# uSlices_v3.net
KiCad netlist of a schematic drawn in EAGLE
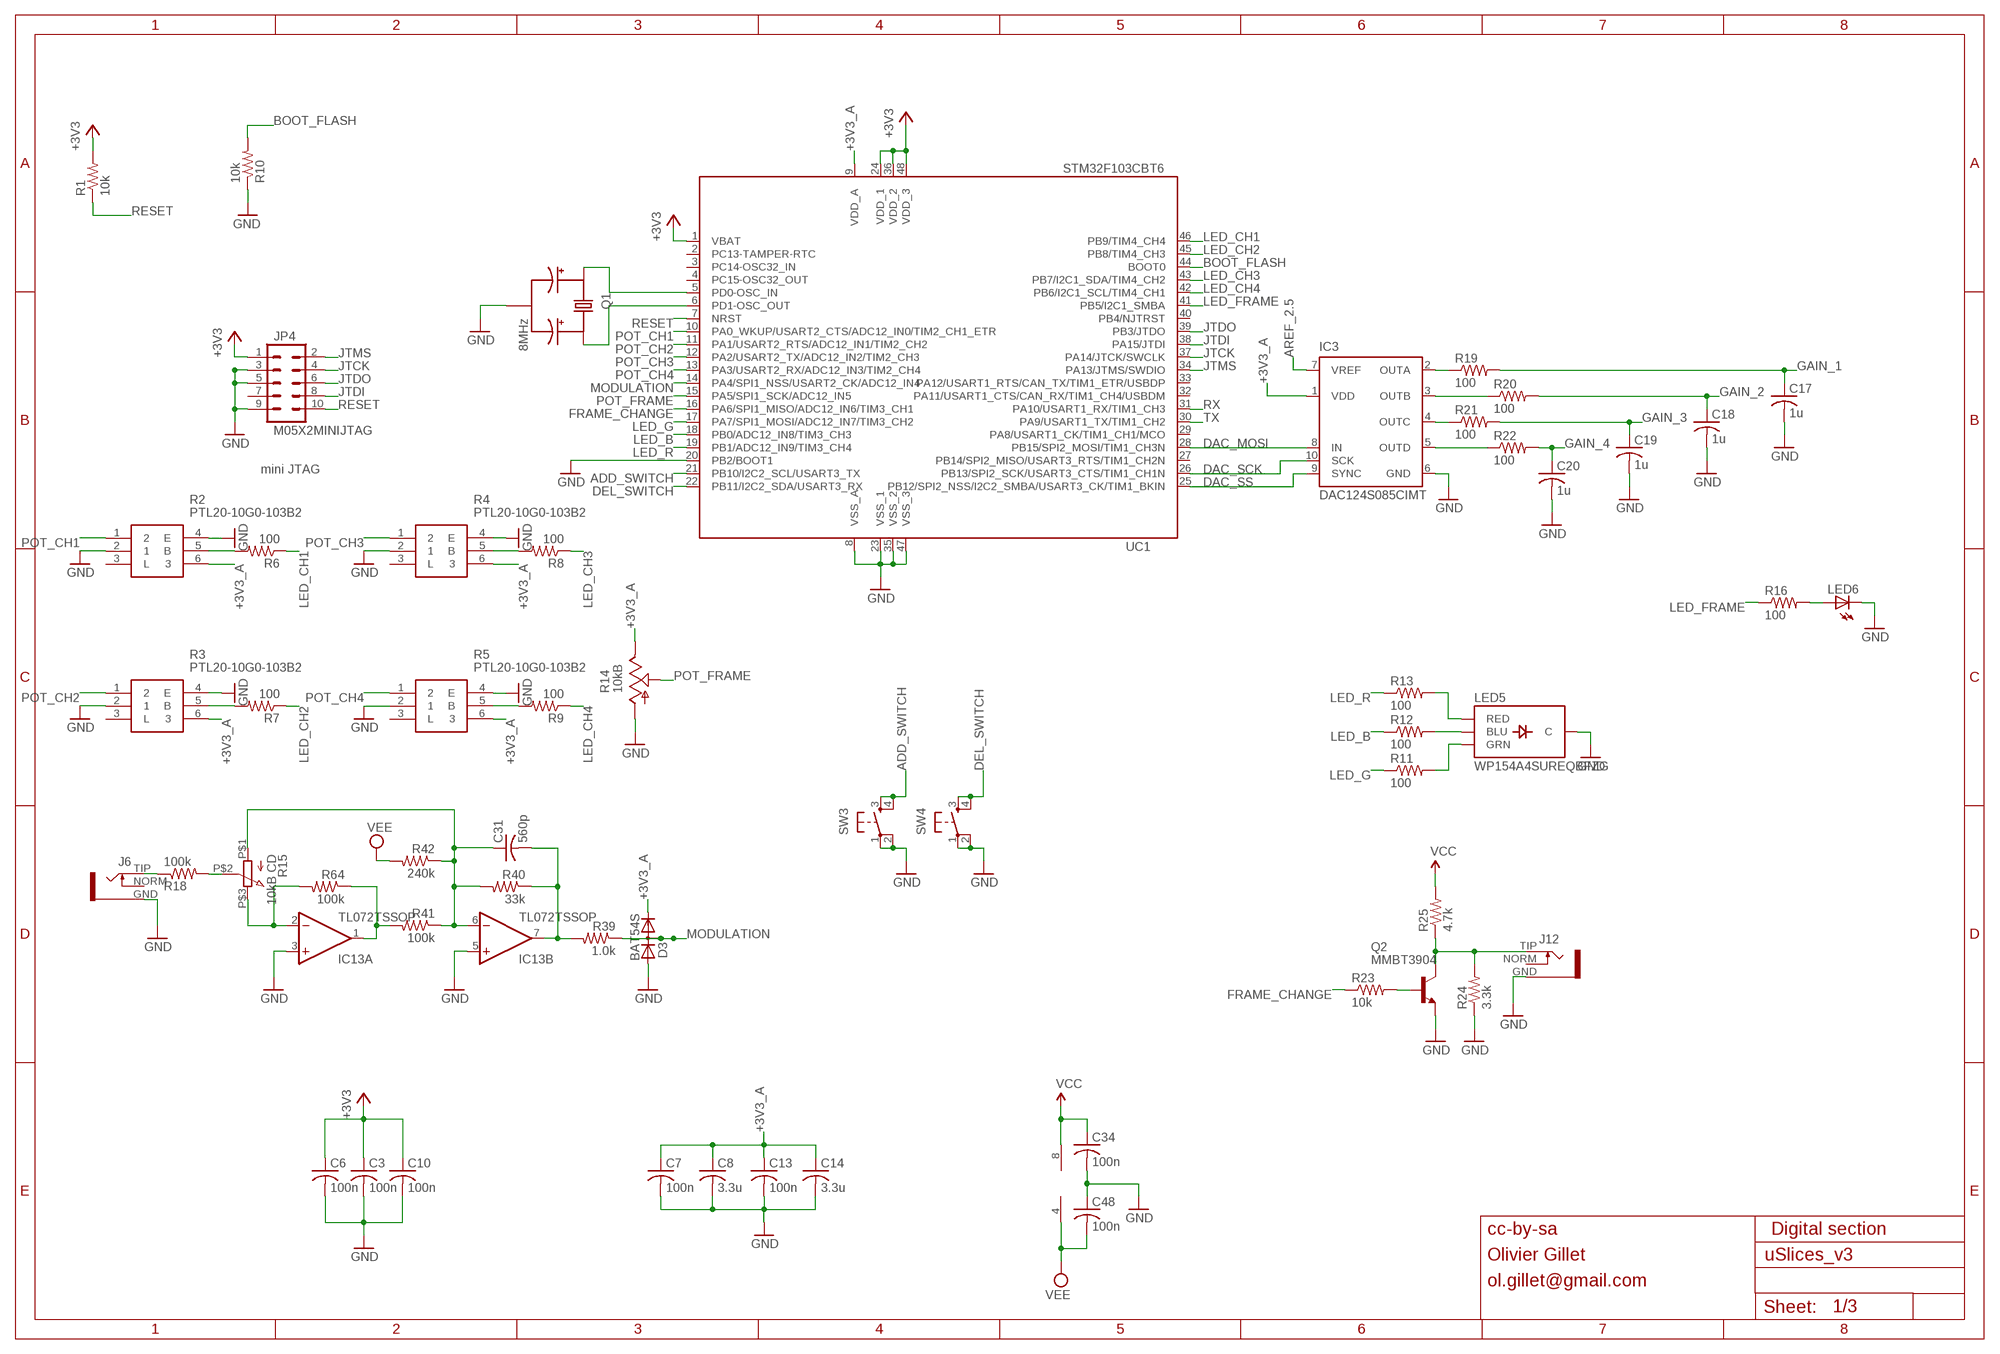
[diagram p0: schematic, sheet 1]
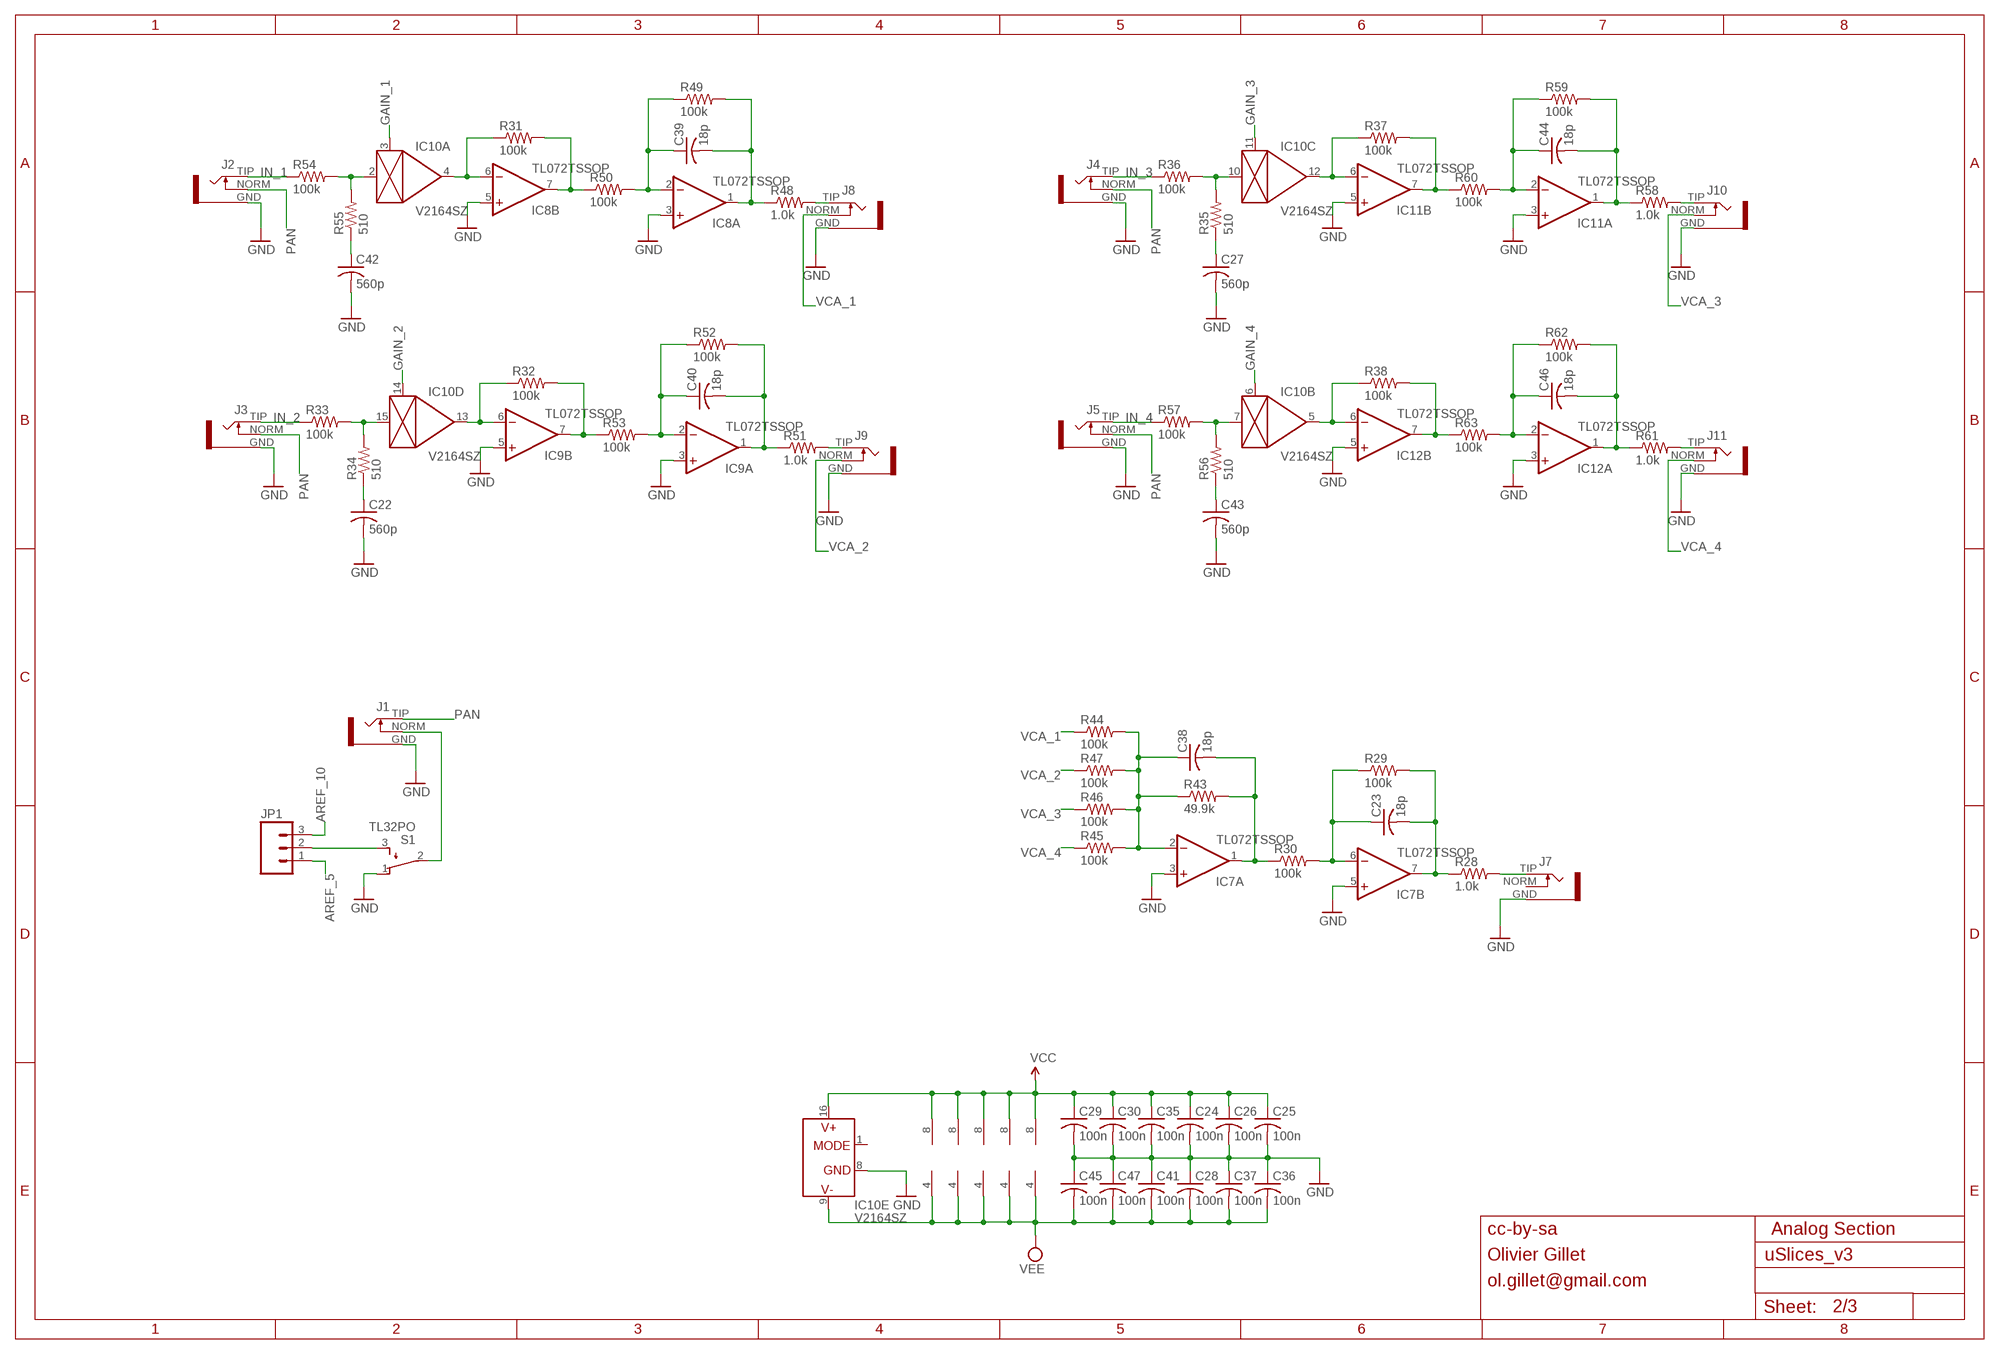
[diagram p1: schematic, sheet 2]
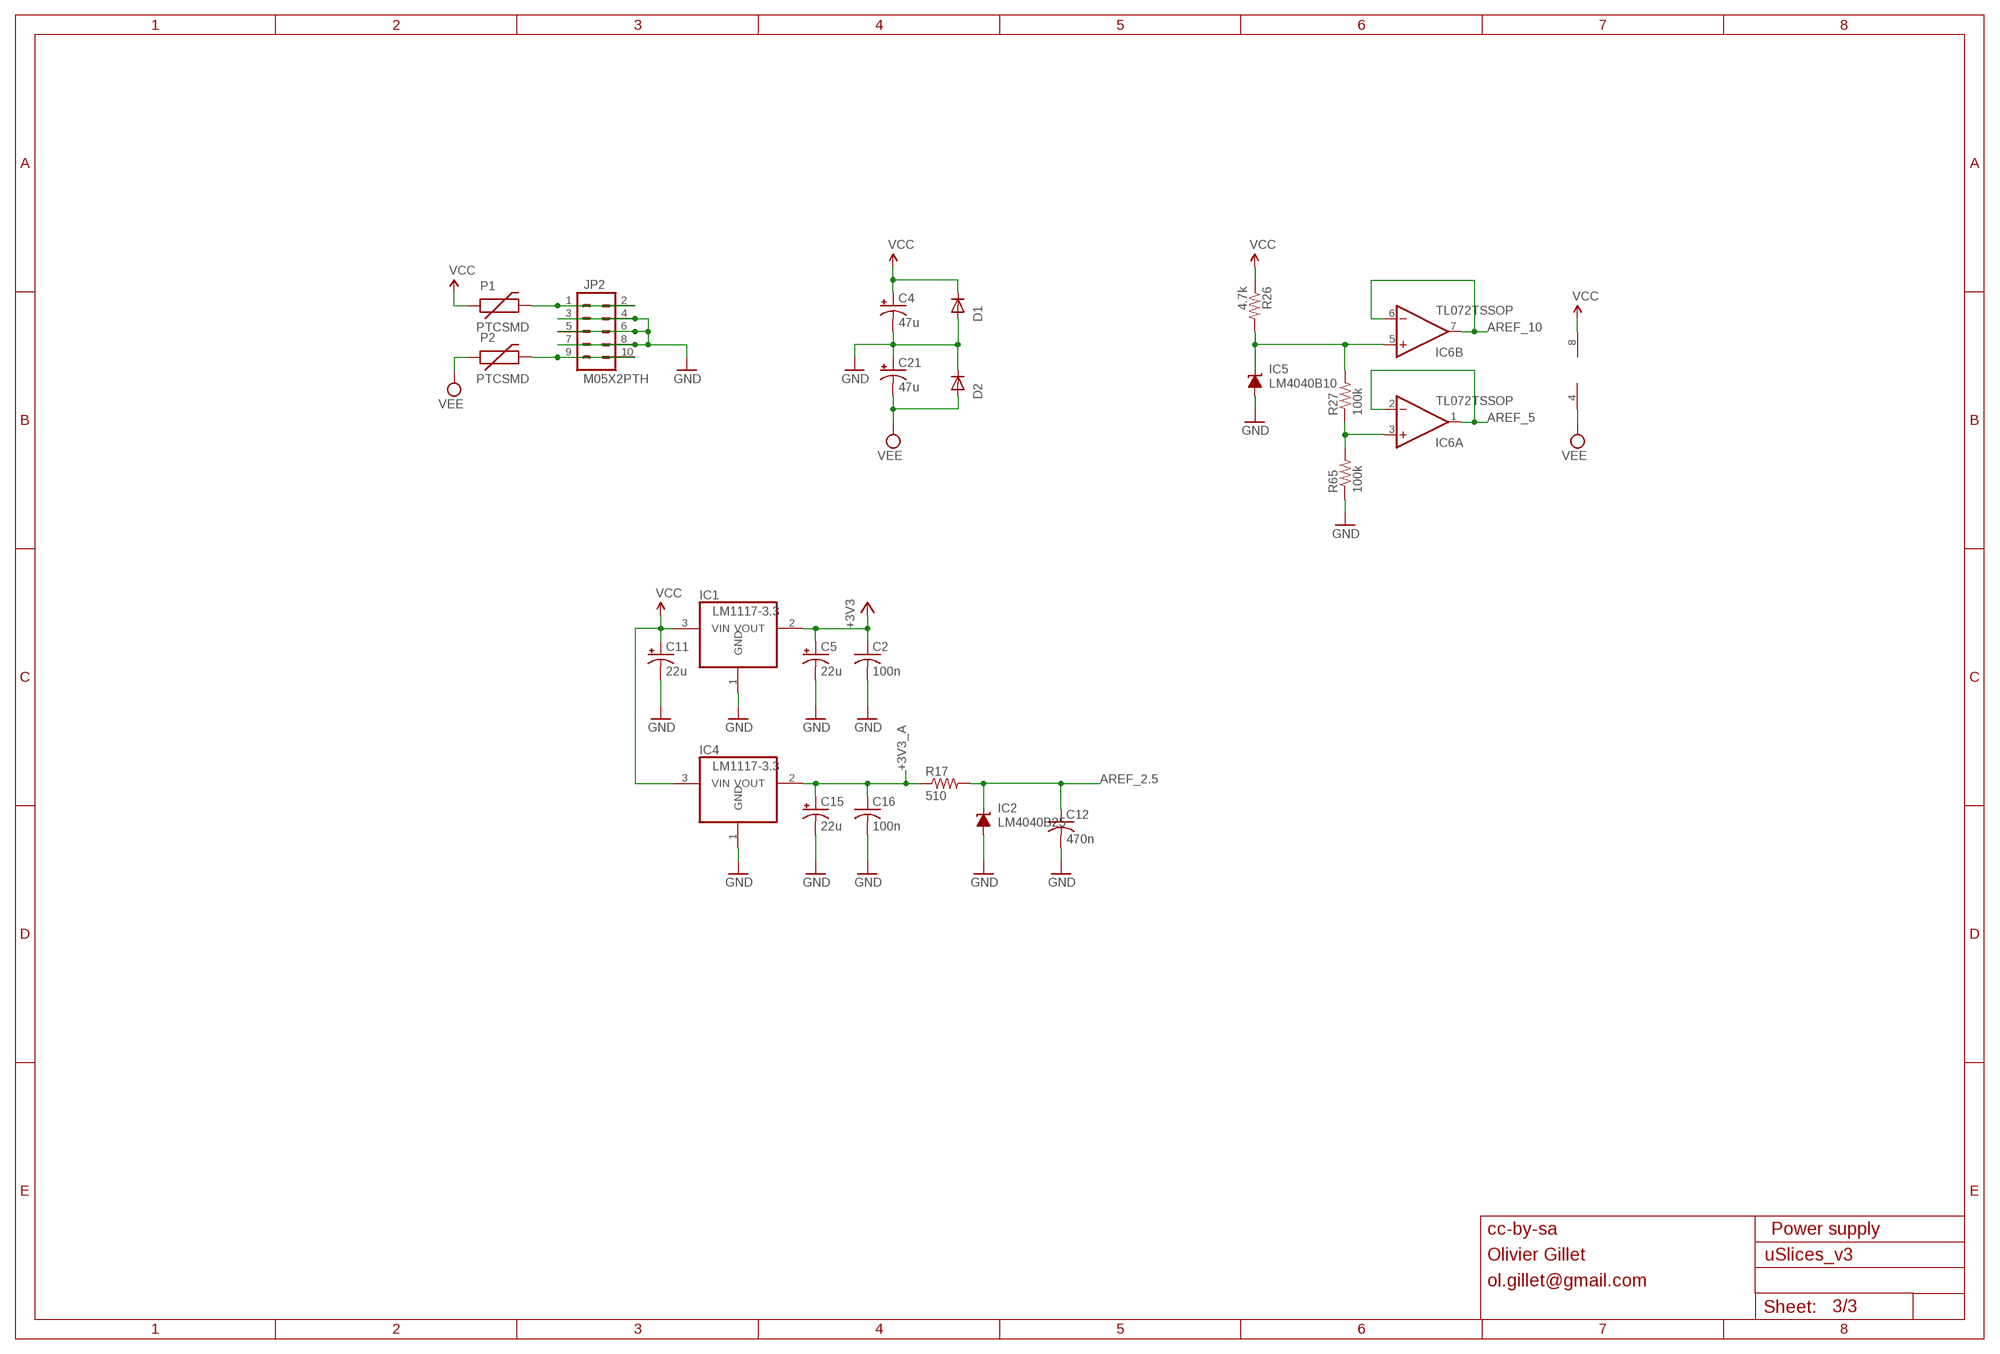
[diagram p2: schematic, sheet 3]

(export (version "E")
  (design (tool "Eeschema 10.0.6"))
  (components
    (comp (ref "C3")
      (value "100n")
      (footprint "eagle-import:C0603")
      (libsource (lib "eagle-import") (part "C-USC0603"))
    )
    (comp (ref "C6")
      (value "100n")
      (footprint "eagle-import:C0603")
      (libsource (lib "eagle-import") (part "C-USC0603"))
    )
    (comp (ref "C7")
      (value "100n")
      (footprint "eagle-import:C0603")
      (libsource (lib "eagle-import") (part "C-USC0603"))
    )
    (comp (ref "C8")
      (value "3.3u")
      (footprint "eagle-import:C0603")
      (libsource (lib "eagle-import") (part "C-USC0603"))
    )
    (comp (ref "C10")
      (value "100n")
      (footprint "eagle-import:C0603")
      (libsource (lib "eagle-import") (part "C-USC0603"))
    )
    (comp (ref "C13")
      (value "100n")
      (footprint "eagle-import:C0603")
      (libsource (lib "eagle-import") (part "C-USC0603"))
    )
    (comp (ref "C14")
      (value "3.3u")
      (footprint "eagle-import:C0603")
      (libsource (lib "eagle-import") (part "C-USC0603"))
    )
    (comp (ref "C17")
      (value "1u")
      (footprint "eagle-import:C0603")
      (libsource (lib "eagle-import") (part "C-USC0603"))
    )
    (comp (ref "C18")
      (value "1u")
      (footprint "eagle-import:C0603")
      (libsource (lib "eagle-import") (part "C-USC0603"))
    )
    (comp (ref "C19")
      (value "1u")
      (footprint "eagle-import:C0603")
      (libsource (lib "eagle-import") (part "C-USC0603"))
    )
    (comp (ref "C20")
      (value "1u")
      (footprint "eagle-import:C0603")
      (libsource (lib "eagle-import") (part "C-USC0603"))
    )
    (comp (ref "C31")
      (value "560p")
      (footprint "eagle-import:C0603")
      (libsource (lib "eagle-import") (part "C-USC0603"))
    )
    (comp (ref "C34")
      (value "100n")
      (footprint "eagle-import:C0603")
      (libsource (lib "eagle-import") (part "C-USC0603"))
    )
    (comp (ref "C48")
      (value "100n")
      (footprint "eagle-import:C0603")
      (libsource (lib "eagle-import") (part "C-USC0603"))
    )
    (comp (ref "D3")
      (value "BAT54S")
      (footprint "eagle-import:SOT23")
      (libsource (lib "eagle-import") (part "DIODE_2CACA-SOT23"))
    )
    (comp (ref "IC3")
      (value "DAC124S085CIMT")
      (footprint "eagle-import:MSOP10")
      (libsource (lib "eagle-import") (part "DAC124S085CIMT"))
    )
    (comp (ref "IC13")
      (value "TL072TSSOP")
      (footprint "eagle-import:TSSOP-8")
      (libsource (lib "eagle-import") (part "TL072TSSOP"))
    )
    (comp (ref "J6")
      (value "INSTRUO_S_JACK_S2_INV")
      (footprint "eagle-import:INSTRUO_S_JACK_S2_INV")
      (libsource (lib "eagle-import") (part "INSTRUO_S_JACK_S2_INV"))
    )
    (comp (ref "J12")
      (value "INSTRUO_S_JACK_S2_INV")
      (footprint "eagle-import:INSTRUO_S_JACK_S2_INV")
      (libsource (lib "eagle-import") (part "INSTRUO_S_JACK_S2_INV"))
    )
    (comp (ref "JP4")
      (value "M05X2MINIJTAG")
      (footprint "eagle-import:2X5-1.27")
      (libsource (lib "eagle-import") (part "M05X2MINIJTAG"))
    )
    (comp (ref "LED5")
      (value "WP154A4SUREQBFZG")
      (footprint "eagle-import:LED-TRICOLOR-THROUGHHOLE")
      (libsource (lib "eagle-import") (part "LED-TRICOLOR-THROUGHHOLE"))
    )
    (comp (ref "LED6")
      (value "LED3MM")
      (footprint "eagle-import:LED3MM")
      (libsource (lib "eagle-import") (part "LED3MM"))
    )
    (comp (ref "Q1")
      (value "8MHz")
      (footprint "eagle-import:INSTRUO_CRYSTAL_SMALLER")
      (libsource (lib "eagle-import") (part "INSTRUO_CRYSTAL_SMALLER"))
    )
    (comp (ref "Q2")
      (value "MMBT3904")
      (footprint "eagle-import:SOT23-BEC")
      (libsource (lib "eagle-import") (part "-NPN-SOT23-BECMMBT3904LT1"))
    )
    (comp (ref "R1")
      (value "10k")
      (footprint "eagle-import:R0603")
      (libsource (lib "eagle-import") (part "R-US_R0603"))
    )
    (comp (ref "R2")
      (value "PTL20-10G0-103B2")
      (footprint "eagle-import:PTL2010G0103B2")
      (fields (field (name "ARROW_PART_NUMBER") "PTL30-10O1-103B2"))
      (libsource (lib "eagle-import") (part "PTL20-10G0-103B2"))
    )
    (comp (ref "R3")
      (value "PTL20-10G0-103B2")
      (footprint "eagle-import:PTL2010G0103B2")
      (fields (field (name "ARROW_PART_NUMBER") "PTL30-10O1-103B2"))
      (libsource (lib "eagle-import") (part "PTL20-10G0-103B2"))
    )
    (comp (ref "R4")
      (value "PTL20-10G0-103B2")
      (footprint "eagle-import:PTL2010G0103B2")
      (fields (field (name "ARROW_PART_NUMBER") "PTL30-10O1-103B2"))
      (libsource (lib "eagle-import") (part "PTL20-10G0-103B2"))
    )
    (comp (ref "R5")
      (value "PTL20-10G0-103B2")
      (footprint "eagle-import:PTL2010G0103B2")
      (fields (field (name "ARROW_PART_NUMBER") "PTL30-10O1-103B2"))
      (libsource (lib "eagle-import") (part "PTL20-10G0-103B2"))
    )
    (comp (ref "R6")
      (value "100")
      (footprint "eagle-import:R0603")
      (libsource (lib "eagle-import") (part "R-US_R0603"))
    )
    (comp (ref "R7")
      (value "100")
      (footprint "eagle-import:R0603")
      (libsource (lib "eagle-import") (part "R-US_R0603"))
    )
    (comp (ref "R8")
      (value "100")
      (footprint "eagle-import:R0603")
      (libsource (lib "eagle-import") (part "R-US_R0603"))
    )
    (comp (ref "R9")
      (value "100")
      (footprint "eagle-import:R0603")
      (libsource (lib "eagle-import") (part "R-US_R0603"))
    )
    (comp (ref "R10")
      (value "10k")
      (footprint "eagle-import:R0603")
      (libsource (lib "eagle-import") (part "R-US_R0603"))
    )
    (comp (ref "R11")
      (value "100")
      (footprint "eagle-import:R0603")
      (libsource (lib "eagle-import") (part "R-US_R0603"))
    )
    (comp (ref "R12")
      (value "100")
      (footprint "eagle-import:R0603")
      (libsource (lib "eagle-import") (part "R-US_R0603"))
    )
    (comp (ref "R13")
      (value "100")
      (footprint "eagle-import:R0603")
      (libsource (lib "eagle-import") (part "R-US_R0603"))
    )
    (comp (ref "R14")
      (value "10kB")
      (footprint "eagle-import:ALPS_POT_VERTICAL_PS")
      (libsource (lib "eagle-import") (part "POT_USVERTICAL_PS"))
    )
    (comp (ref "R15")
      (value "10kB CD")
      (footprint "eagle-import:INSTRUO_Q-POT2")
      (libsource (lib "eagle-import") (part "INSTRUO_Q-POT2"))
    )
    (comp (ref "R16")
      (value "100")
      (footprint "eagle-import:R0603")
      (libsource (lib "eagle-import") (part "R-US_R0603"))
    )
    (comp (ref "R18")
      (value "100k")
      (footprint "eagle-import:R0603")
      (libsource (lib "eagle-import") (part "R-US_R0603"))
    )
    (comp (ref "R19")
      (value "100")
      (footprint "eagle-import:R0603")
      (libsource (lib "eagle-import") (part "R-US_R0603"))
    )
    (comp (ref "R20")
      (value "100")
      (footprint "eagle-import:R0603")
      (libsource (lib "eagle-import") (part "R-US_R0603"))
    )
    (comp (ref "R21")
      (value "100")
      (footprint "eagle-import:R0603")
      (libsource (lib "eagle-import") (part "R-US_R0603"))
    )
    (comp (ref "R22")
      (value "100")
      (footprint "eagle-import:R0603")
      (libsource (lib "eagle-import") (part "R-US_R0603"))
    )
    (comp (ref "R23")
      (value "10k")
      (footprint "eagle-import:R0603")
      (libsource (lib "eagle-import") (part "R-US_R0603"))
    )
    (comp (ref "R24")
      (value "3.3k")
      (footprint "eagle-import:R0603")
      (libsource (lib "eagle-import") (part "R-US_R0603"))
    )
    (comp (ref "R25")
      (value "4.7k")
      (footprint "eagle-import:R0603")
      (libsource (lib "eagle-import") (part "R-US_R0603"))
    )
    (comp (ref "R39")
      (value "1.0k")
      (footprint "eagle-import:R0603")
      (libsource (lib "eagle-import") (part "R-US_R0603"))
    )
    (comp (ref "R40")
      (value "33k")
      (footprint "eagle-import:R0603")
      (libsource (lib "eagle-import") (part "R-US_R0603"))
    )
    (comp (ref "R41")
      (value "100k")
      (footprint "eagle-import:R0603")
      (libsource (lib "eagle-import") (part "R-US_R0603"))
    )
    (comp (ref "R42")
      (value "240k")
      (footprint "eagle-import:R0603")
      (libsource (lib "eagle-import") (part "R-US_R0603"))
    )
    (comp (ref "R64")
      (value "100k")
      (footprint "eagle-import:R0603")
      (libsource (lib "eagle-import") (part "R-US_R0603"))
    )
    (comp (ref "SW3")
      (value "SPARKFUN_TAC_SWITCHPTH")
      (footprint "eagle-import:SPARKFUN_TACTILE-PTH")
      (libsource (lib "eagle-import") (part "SPARKFUN_TAC_SWITCHPTH"))
    )
    (comp (ref "SW4")
      (value "SPARKFUN_TAC_SWITCHPTH")
      (footprint "eagle-import:SPARKFUN_TACTILE-PTH")
      (libsource (lib "eagle-import") (part "SPARKFUN_TAC_SWITCHPTH"))
    )
    (comp (ref "UC1")
      (value "STM32F103CBT6")
      (footprint "eagle-import:LQFP48")
      (libsource (lib "eagle-import") (part "STM32F103CB"))
    )
    (comp (ref "C2")
      (value "100n")
      (footprint "eagle-import:C0603")
      (libsource (lib "eagle-import") (part "C-USC0603"))
    )
    (comp (ref "C4")
      (value "47u")
      (footprint "eagle-import:PANASONIC_D")
      (libsource (lib "eagle-import") (part "CPOL-USD"))
    )
    (comp (ref "C5")
      (value "22u")
      (footprint "eagle-import:PANASONIC_C")
      (libsource (lib "eagle-import") (part "CPOL-USC"))
    )
    (comp (ref "C11")
      (value "22u")
      (footprint "eagle-import:PANASONIC_C")
      (libsource (lib "eagle-import") (part "CPOL-USC"))
    )
    (comp (ref "C12")
      (value "470n")
      (footprint "eagle-import:C0603")
      (libsource (lib "eagle-import") (part "C-USC0603"))
    )
    (comp (ref "C15")
      (value "22u")
      (footprint "eagle-import:PANASONIC_C")
      (libsource (lib "eagle-import") (part "CPOL-USC"))
    )
    (comp (ref "C16")
      (value "100n")
      (footprint "eagle-import:C0603")
      (libsource (lib "eagle-import") (part "C-USC0603"))
    )
    (comp (ref "C21")
      (value "47u")
      (footprint "eagle-import:PANASONIC_D")
      (libsource (lib "eagle-import") (part "CPOL-USD"))
    )
    (comp (ref "D1")
      (value "1N5819HW")
      (footprint "eagle-import:SOD123")
      (libsource (lib "eagle-import") (part "DIODE-SOD123"))
    )
    (comp (ref "D2")
      (value "1N5819HW")
      (footprint "eagle-import:SOD123")
      (libsource (lib "eagle-import") (part "DIODE-SOD123"))
    )
    (comp (ref "IC1")
      (value "LM1117-3.3")
      (footprint "eagle-import:SOT223")
      (libsource (lib "eagle-import") (part "REG1117"))
    )
    (comp (ref "IC2")
      (value "LM4040B25")
      (footprint "eagle-import:DBZ_R-PDSO-G3")
      (libsource (lib "eagle-import") (part "LM4041DBZB12"))
    )
    (comp (ref "IC4")
      (value "LM1117-3.3")
      (footprint "eagle-import:SOT223")
      (libsource (lib "eagle-import") (part "REG1117"))
    )
    (comp (ref "IC5")
      (value "LM4040B10")
      (footprint "eagle-import:DBZ_R-PDSO-G3")
      (libsource (lib "eagle-import") (part "LM4041DBZB12"))
    )
    (comp (ref "IC6")
      (value "TL072TSSOP")
      (footprint "eagle-import:TSSOP-8")
      (libsource (lib "eagle-import") (part "TL072TSSOP"))
    )
    (comp (ref "JP2")
      (value "M05X2PTH")
      (footprint "eagle-import:AVR_ICSP")
      (libsource (lib "eagle-import") (part "M05X2PTH"))
    )
    (comp (ref "P1")
      (value "PTCSMD")
      (footprint "eagle-import:PTC-1206")
      (libsource (lib "eagle-import") (part "PTCSMD"))
    )
    (comp (ref "P2")
      (value "PTCSMD")
      (footprint "eagle-import:PTC-1206")
      (libsource (lib "eagle-import") (part "PTCSMD"))
    )
    (comp (ref "R17")
      (value "510")
      (footprint "eagle-import:R0603")
      (libsource (lib "eagle-import") (part "R-US_R0603"))
    )
    (comp (ref "R26")
      (value "4.7k")
      (footprint "eagle-import:R0603")
      (libsource (lib "eagle-import") (part "R-US_R0603"))
    )
    (comp (ref "R27")
      (value "100k")
      (footprint "eagle-import:R0603")
      (libsource (lib "eagle-import") (part "R-US_R0603"))
    )
    (comp (ref "R65")
      (value "100k")
      (footprint "eagle-import:R0603")
      (libsource (lib "eagle-import") (part "R-US_R0603"))
    )
    (comp (ref "C22")
      (value "560p")
      (footprint "eagle-import:C0603")
      (libsource (lib "eagle-import") (part "C-USC0603"))
    )
    (comp (ref "C23")
      (value "18p")
      (footprint "eagle-import:C0603")
      (libsource (lib "eagle-import") (part "C-USC0603"))
    )
    (comp (ref "C24")
      (value "100n")
      (footprint "eagle-import:C0603")
      (libsource (lib "eagle-import") (part "C-USC0603"))
    )
    (comp (ref "C25")
      (value "100n")
      (footprint "eagle-import:C0603")
      (libsource (lib "eagle-import") (part "C-USC0603"))
    )
    (comp (ref "C26")
      (value "100n")
      (footprint "eagle-import:C0603")
      (libsource (lib "eagle-import") (part "C-USC0603"))
    )
    (comp (ref "C27")
      (value "560p")
      (footprint "eagle-import:C0603")
      (libsource (lib "eagle-import") (part "C-USC0603"))
    )
    (comp (ref "C28")
      (value "100n")
      (footprint "eagle-import:C0603")
      (libsource (lib "eagle-import") (part "C-USC0603"))
    )
    (comp (ref "C29")
      (value "100n")
      (footprint "eagle-import:C0603")
      (libsource (lib "eagle-import") (part "C-USC0603"))
    )
    (comp (ref "C30")
      (value "100n")
      (footprint "eagle-import:C0603")
      (libsource (lib "eagle-import") (part "C-USC0603"))
    )
    (comp (ref "C35")
      (value "100n")
      (footprint "eagle-import:C0603")
      (libsource (lib "eagle-import") (part "C-USC0603"))
    )
    (comp (ref "C36")
      (value "100n")
      (footprint "eagle-import:C0603")
      (libsource (lib "eagle-import") (part "C-USC0603"))
    )
    (comp (ref "C37")
      (value "100n")
      (footprint "eagle-import:C0603")
      (libsource (lib "eagle-import") (part "C-USC0603"))
    )
    (comp (ref "C38")
      (value "18p")
      (footprint "eagle-import:C0603")
      (libsource (lib "eagle-import") (part "C-USC0603"))
    )
    (comp (ref "C39")
      (value "18p")
      (footprint "eagle-import:C0603")
      (libsource (lib "eagle-import") (part "C-USC0603"))
    )
    (comp (ref "C40")
      (value "18p")
      (footprint "eagle-import:C0603")
      (libsource (lib "eagle-import") (part "C-USC0603"))
    )
    (comp (ref "C41")
      (value "100n")
      (footprint "eagle-import:C0603")
      (libsource (lib "eagle-import") (part "C-USC0603"))
    )
    (comp (ref "C42")
      (value "560p")
      (footprint "eagle-import:C0603")
      (libsource (lib "eagle-import") (part "C-USC0603"))
    )
    (comp (ref "C43")
      (value "560p")
      (footprint "eagle-import:C0603")
      (libsource (lib "eagle-import") (part "C-USC0603"))
    )
    (comp (ref "C44")
      (value "18p")
      (footprint "eagle-import:C0603")
      (libsource (lib "eagle-import") (part "C-USC0603"))
    )
    (comp (ref "C45")
      (value "100n")
      (footprint "eagle-import:C0603")
      (libsource (lib "eagle-import") (part "C-USC0603"))
    )
    (comp (ref "C46")
      (value "18p")
      (footprint "eagle-import:C0603")
      (libsource (lib "eagle-import") (part "C-USC0603"))
    )
    (comp (ref "C47")
      (value "100n")
      (footprint "eagle-import:C0603")
      (libsource (lib "eagle-import") (part "C-USC0603"))
    )
    (comp (ref "IC7")
      (value "TL072TSSOP")
      (footprint "eagle-import:TSSOP-8")
      (libsource (lib "eagle-import") (part "TL072TSSOP"))
    )
    (comp (ref "IC8")
      (value "TL072TSSOP")
      (footprint "eagle-import:TSSOP-8")
      (libsource (lib "eagle-import") (part "TL072TSSOP"))
    )
    (comp (ref "IC9")
      (value "TL072TSSOP")
      (footprint "eagle-import:TSSOP-8")
      (libsource (lib "eagle-import") (part "TL072TSSOP"))
    )
    (comp (ref "IC10")
      (value "V2164SZ")
      (footprint "eagle-import:SOIC16N")
      (libsource (lib "eagle-import") (part "SSM2164S"))
    )
    (comp (ref "IC11")
      (value "TL072TSSOP")
      (footprint "eagle-import:TSSOP-8")
      (libsource (lib "eagle-import") (part "TL072TSSOP"))
    )
    (comp (ref "IC12")
      (value "TL072TSSOP")
      (footprint "eagle-import:TSSOP-8")
      (libsource (lib "eagle-import") (part "TL072TSSOP"))
    )
    (comp (ref "J1")
      (value "INSTRUO_S_JACK_S2_INV")
      (footprint "eagle-import:INSTRUO_S_JACK_S2_INV")
      (libsource (lib "eagle-import") (part "INSTRUO_S_JACK_S2_INV"))
    )
    (comp (ref "J2")
      (value "INSTRUO_S_JACK_S2_INV")
      (footprint "eagle-import:INSTRUO_S_JACK_S2_INV")
      (libsource (lib "eagle-import") (part "INSTRUO_S_JACK_S2_INV"))
    )
    (comp (ref "J3")
      (value "INSTRUO_S_JACK_S2_INV")
      (footprint "eagle-import:INSTRUO_S_JACK_S2_INV")
      (libsource (lib "eagle-import") (part "INSTRUO_S_JACK_S2_INV"))
    )
    (comp (ref "J4")
      (value "INSTRUO_S_JACK_S2_INV")
      (footprint "eagle-import:INSTRUO_S_JACK_S2_INV")
      (libsource (lib "eagle-import") (part "INSTRUO_S_JACK_S2_INV"))
    )
    (comp (ref "J5")
      (value "INSTRUO_S_JACK_S2_INV")
      (footprint "eagle-import:INSTRUO_S_JACK_S2_INV")
      (libsource (lib "eagle-import") (part "INSTRUO_S_JACK_S2_INV"))
    )
    (comp (ref "J7")
      (value "INSTRUO_S_JACK_S2_INV")
      (footprint "eagle-import:INSTRUO_S_JACK_S2_INV")
      (libsource (lib "eagle-import") (part "INSTRUO_S_JACK_S2_INV"))
    )
    (comp (ref "J8")
      (value "INSTRUO_S_JACK_S2_INV")
      (footprint "eagle-import:INSTRUO_S_JACK_S2_INV")
      (libsource (lib "eagle-import") (part "INSTRUO_S_JACK_S2_INV"))
    )
    (comp (ref "J9")
      (value "INSTRUO_S_JACK_S2_INV")
      (footprint "eagle-import:INSTRUO_S_JACK_S2_INV")
      (libsource (lib "eagle-import") (part "INSTRUO_S_JACK_S2_INV"))
    )
    (comp (ref "J10")
      (value "INSTRUO_S_JACK_S2_INV")
      (footprint "eagle-import:INSTRUO_S_JACK_S2_INV")
      (libsource (lib "eagle-import") (part "INSTRUO_S_JACK_S2_INV"))
    )
    (comp (ref "J11")
      (value "INSTRUO_S_JACK_S2_INV")
      (footprint "eagle-import:INSTRUO_S_JACK_S2_INV")
      (libsource (lib "eagle-import") (part "INSTRUO_S_JACK_S2_INV"))
    )
    (comp (ref "JP1")
      (value "M03PTH")
      (footprint "eagle-import:1X03")
      (libsource (lib "eagle-import") (part "M03PTH"))
    )
    (comp (ref "R28")
      (value "1.0k")
      (footprint "eagle-import:R0603")
      (libsource (lib "eagle-import") (part "R-US_R0603"))
    )
    (comp (ref "R29")
      (value "100k")
      (footprint "eagle-import:R0603")
      (libsource (lib "eagle-import") (part "R-US_R0603"))
    )
    (comp (ref "R30")
      (value "100k")
      (footprint "eagle-import:R0603")
      (libsource (lib "eagle-import") (part "R-US_R0603"))
    )
    (comp (ref "R31")
      (value "100k")
      (footprint "eagle-import:R0603")
      (libsource (lib "eagle-import") (part "R-US_R0603"))
    )
    (comp (ref "R32")
      (value "100k")
      (footprint "eagle-import:R0603")
      (libsource (lib "eagle-import") (part "R-US_R0603"))
    )
    (comp (ref "R33")
      (value "100k")
      (footprint "eagle-import:R0603")
      (libsource (lib "eagle-import") (part "R-US_R0603"))
    )
    (comp (ref "R34")
      (value "510")
      (footprint "eagle-import:R0603")
      (libsource (lib "eagle-import") (part "R-US_R0603"))
    )
    (comp (ref "R35")
      (value "510")
      (footprint "eagle-import:R0603")
      (libsource (lib "eagle-import") (part "R-US_R0603"))
    )
    (comp (ref "R36")
      (value "100k")
      (footprint "eagle-import:R0603")
      (libsource (lib "eagle-import") (part "R-US_R0603"))
    )
    (comp (ref "R37")
      (value "100k")
      (footprint "eagle-import:R0603")
      (libsource (lib "eagle-import") (part "R-US_R0603"))
    )
    (comp (ref "R38")
      (value "100k")
      (footprint "eagle-import:R0603")
      (libsource (lib "eagle-import") (part "R-US_R0603"))
    )
    (comp (ref "R43")
      (value "49.9k")
      (footprint "eagle-import:R0603")
      (libsource (lib "eagle-import") (part "R-US_R0603"))
    )
    (comp (ref "R44")
      (value "100k")
      (footprint "eagle-import:R0603")
      (libsource (lib "eagle-import") (part "R-US_R0603"))
    )
    (comp (ref "R45")
      (value "100k")
      (footprint "eagle-import:R0603")
      (libsource (lib "eagle-import") (part "R-US_R0603"))
    )
    (comp (ref "R46")
      (value "100k")
      (footprint "eagle-import:R0603")
      (libsource (lib "eagle-import") (part "R-US_R0603"))
    )
    (comp (ref "R47")
      (value "100k")
      (footprint "eagle-import:R0603")
      (libsource (lib "eagle-import") (part "R-US_R0603"))
    )
    (comp (ref "R48")
      (value "1.0k")
      (footprint "eagle-import:R0603")
      (libsource (lib "eagle-import") (part "R-US_R0603"))
    )
    (comp (ref "R49")
      (value "100k")
      (footprint "eagle-import:R0603")
      (libsource (lib "eagle-import") (part "R-US_R0603"))
    )
    (comp (ref "R50")
      (value "100k")
      (footprint "eagle-import:R0603")
      (libsource (lib "eagle-import") (part "R-US_R0603"))
    )
    (comp (ref "R51")
      (value "1.0k")
      (footprint "eagle-import:R0603")
      (libsource (lib "eagle-import") (part "R-US_R0603"))
    )
    (comp (ref "R52")
      (value "100k")
      (footprint "eagle-import:R0603")
      (libsource (lib "eagle-import") (part "R-US_R0603"))
    )
    (comp (ref "R53")
      (value "100k")
      (footprint "eagle-import:R0603")
      (libsource (lib "eagle-import") (part "R-US_R0603"))
    )
    (comp (ref "R54")
      (value "100k")
      (footprint "eagle-import:R0603")
      (libsource (lib "eagle-import") (part "R-US_R0603"))
    )
    (comp (ref "R55")
      (value "510")
      (footprint "eagle-import:R0603")
      (libsource (lib "eagle-import") (part "R-US_R0603"))
    )
    (comp (ref "R56")
      (value "510")
      (footprint "eagle-import:R0603")
      (libsource (lib "eagle-import") (part "R-US_R0603"))
    )
    (comp (ref "R57")
      (value "100k")
      (footprint "eagle-import:R0603")
      (libsource (lib "eagle-import") (part "R-US_R0603"))
    )
    (comp (ref "R58")
      (value "1.0k")
      (footprint "eagle-import:R0603")
      (libsource (lib "eagle-import") (part "R-US_R0603"))
    )
    (comp (ref "R59")
      (value "100k")
      (footprint "eagle-import:R0603")
      (libsource (lib "eagle-import") (part "R-US_R0603"))
    )
    (comp (ref "R60")
      (value "100k")
      (footprint "eagle-import:R0603")
      (libsource (lib "eagle-import") (part "R-US_R0603"))
    )
    (comp (ref "R61")
      (value "1.0k")
      (footprint "eagle-import:R0603")
      (libsource (lib "eagle-import") (part "R-US_R0603"))
    )
    (comp (ref "R62")
      (value "100k")
      (footprint "eagle-import:R0603")
      (libsource (lib "eagle-import") (part "R-US_R0603"))
    )
    (comp (ref "R63")
      (value "100k")
      (footprint "eagle-import:R0603")
      (libsource (lib "eagle-import") (part "R-US_R0603"))
    )
    (comp (ref "S1")
      (value "TL32PO")
      (footprint "eagle-import:TL3XPO")
      (libsource (lib "eagle-import") (part "TL32PO"))
    )
  )
  (nets
    (net (code "1") (name "+3V3") (class "Default")
      (node (ref "C10") (pin "1") (pinfunction "1_1") (pintype "passive"))
      (node (ref "C2") (pin "1") (pinfunction "1_1") (pintype "passive"))
      (node (ref "C3") (pin "1") (pinfunction "1_1") (pintype "passive"))
      (node (ref "C5") (pin "+") (pinfunction "+_+") (pintype "passive"))
      (node (ref "C6") (pin "1") (pinfunction "1_1") (pintype "passive"))
      (node (ref "IC1") (pin "2") (pinfunction "VOUT_2") (pintype "output"))
      (node (ref "JP4") (pin "1") (pinfunction "1_1") (pintype "passive"))
      (node (ref "R1") (pin "2") (pinfunction "2_2") (pintype "passive"))
      (node (ref "UC1") (pin "1") (pinfunction "VBAT_1") (pintype "power_in"))
      (node (ref "UC1") (pin "24") (pinfunction "VDD_1_24") (pintype "power_in"))
      (node (ref "UC1") (pin "36") (pinfunction "VDD_2_36") (pintype "power_in"))
      (node (ref "UC1") (pin "48") (pinfunction "VDD_3_48") (pintype "power_in"))
    )
    (net (code "2") (name "+3V3_A") (class "Default")
      (node (ref "C13") (pin "1") (pinfunction "1_1") (pintype "passive"))
      (node (ref "C14") (pin "1") (pinfunction "1_1") (pintype "passive"))
      (node (ref "C15") (pin "+") (pinfunction "+_+") (pintype "passive"))
      (node (ref "C16") (pin "1") (pinfunction "1_1") (pintype "passive"))
      (node (ref "C7") (pin "1") (pinfunction "1_1") (pintype "passive"))
      (node (ref "C8") (pin "1") (pinfunction "1_1") (pintype "passive"))
      (node (ref "D3") (pin "2") (pinfunction "C_2") (pintype "passive"))
      (node (ref "IC3") (pin "1") (pinfunction "VDD_1") (pintype "power_in"))
      (node (ref "IC4") (pin "2") (pinfunction "VOUT_2") (pintype "output"))
      (node (ref "R14") (pin "P$1") (pinfunction "E_P$1") (pintype "passive"))
      (node (ref "R17") (pin "1") (pinfunction "1_1") (pintype "passive"))
      (node (ref "R2") (pin "6") (pinfunction "3_6") (pintype "bidirectional"))
      (node (ref "R3") (pin "6") (pinfunction "3_6") (pintype "bidirectional"))
      (node (ref "R4") (pin "6") (pinfunction "3_6") (pintype "bidirectional"))
      (node (ref "R5") (pin "6") (pinfunction "3_6") (pintype "bidirectional"))
      (node (ref "UC1") (pin "9") (pinfunction "VDD_A_9") (pintype "power_in"))
    )
    (net (code "3") (name "ADD_SWITCH") (class "Default")
      (node (ref "SW3") (pin "3") (pinfunction "3_3") (pintype "passive"))
      (node (ref "SW3") (pin "4") (pinfunction "4_4") (pintype "passive"))
      (node (ref "UC1") (pin "21") (pinfunction "PB10/I2C2_SCL/USART3_TX_21") (pintype "input"))
    )
    (net (code "4") (name "AREF_2.5") (class "Default")
      (node (ref "C12") (pin "1") (pinfunction "1_1") (pintype "passive"))
      (node (ref "IC2") (pin "1") (pinfunction "C_1") (pintype "passive"))
      (node (ref "IC3") (pin "7") (pinfunction "VREF_7") (pintype "bidirectional"))
      (node (ref "R17") (pin "2") (pinfunction "2_2") (pintype "passive"))
    )
    (net (code "5") (name "AREF_5") (class "Default")
      (node (ref "IC6") (pin "1") (pinfunction "OUT_1") (pintype "output"))
      (node (ref "IC6") (pin "2") (pinfunction "-IN_2") (pintype "input"))
      (node (ref "JP1") (pin "1") (pinfunction "1_1") (pintype "passive"))
    )
    (net (code "6") (name "AREF_10") (class "Default")
      (node (ref "IC6") (pin "6") (pinfunction "-IN_6") (pintype "input"))
      (node (ref "IC6") (pin "7") (pinfunction "OUT_7") (pintype "output"))
      (node (ref "JP1") (pin "3") (pinfunction "3_3") (pintype "passive"))
    )
    (net (code "7") (name "BOOT_FLASH") (class "Default")
      (node (ref "R10") (pin "2") (pinfunction "2_2") (pintype "passive"))
      (node (ref "UC1") (pin "44") (pinfunction "BOOT0_44") (pintype "input"))
    )
    (net (code "8") (name "DAC_MOSI") (class "Default")
      (node (ref "IC3") (pin "8") (pinfunction "IN_8") (pintype "input"))
      (node (ref "UC1") (pin "28") (pinfunction "PB15/SPI2_MOSI/TIM1_CH3N_28") (pintype "input"))
    )
    (net (code "9") (name "DAC_SCK") (class "Default")
      (node (ref "IC3") (pin "10") (pinfunction "SCK_10") (pintype "input"))
      (node (ref "UC1") (pin "26") (pinfunction "PB13/SPI2_SCK/USART3_CTS/TIM1_CH1N_26") (pintype "input"))
    )
    (net (code "10") (name "DAC_SS") (class "Default")
      (node (ref "IC3") (pin "9") (pinfunction "SYNC_9") (pintype "input"))
      (node (ref "UC1") (pin "25") (pinfunction "PB12/SPI2_NSS/I2C2_SMBA/USART3_CK/TIM1_BKIN_25") (pintype "input"))
    )
    (net (code "11") (name "DEL_SWITCH") (class "Default")
      (node (ref "SW4") (pin "3") (pinfunction "3_3") (pintype "passive"))
      (node (ref "SW4") (pin "4") (pinfunction "4_4") (pintype "passive"))
      (node (ref "UC1") (pin "22") (pinfunction "PB11/I2C2_SDA/USART3_RX_22") (pintype "input"))
    )
    (net (code "12") (name "FRAME_CHANGE") (class "Default")
      (node (ref "R23") (pin "1") (pinfunction "1_1") (pintype "passive"))
      (node (ref "UC1") (pin "16") (pinfunction "PA6/SPI1_MISO/ADC12_IN6/TIM3_CH1_16") (pintype "bidirectional"))
    )
    (net (code "13") (name "GAIN_1") (class "Default")
      (node (ref "C17") (pin "1") (pinfunction "1_1") (pintype "passive"))
      (node (ref "IC10") (pin "3") (pinfunction "CTRL_3") (pintype "input"))
      (node (ref "R19") (pin "2") (pinfunction "2_2") (pintype "passive"))
    )
    (net (code "14") (name "GAIN_2") (class "Default")
      (node (ref "C18") (pin "1") (pinfunction "1_1") (pintype "passive"))
      (node (ref "IC10") (pin "14") (pinfunction "CTRL_14") (pintype "input"))
      (node (ref "R20") (pin "2") (pinfunction "2_2") (pintype "passive"))
    )
    (net (code "15") (name "GAIN_3") (class "Default")
      (node (ref "C19") (pin "1") (pinfunction "1_1") (pintype "passive"))
      (node (ref "IC10") (pin "11") (pinfunction "CTRL_11") (pintype "input"))
      (node (ref "R21") (pin "2") (pinfunction "2_2") (pintype "passive"))
    )
    (net (code "16") (name "GAIN_4") (class "Default")
      (node (ref "C20") (pin "1") (pinfunction "1_1") (pintype "passive"))
      (node (ref "IC10") (pin "6") (pinfunction "CTRL_6") (pintype "input"))
      (node (ref "R22") (pin "2") (pinfunction "2_2") (pintype "passive"))
    )
    (net (code "17") (name "GND") (class "Default")
      (node (ref "C10") (pin "2") (pinfunction "2_2") (pintype "passive"))
      (node (ref "C11") (pin "-") (pinfunction "-_-") (pintype "passive"))
      (node (ref "C12") (pin "2") (pinfunction "2_2") (pintype "passive"))
      (node (ref "C13") (pin "2") (pinfunction "2_2") (pintype "passive"))
      (node (ref "C14") (pin "2") (pinfunction "2_2") (pintype "passive"))
      (node (ref "C15") (pin "-") (pinfunction "-_-") (pintype "passive"))
      (node (ref "C16") (pin "2") (pinfunction "2_2") (pintype "passive"))
      (node (ref "C17") (pin "2") (pinfunction "2_2") (pintype "passive"))
      (node (ref "C18") (pin "2") (pinfunction "2_2") (pintype "passive"))
      (node (ref "C19") (pin "2") (pinfunction "2_2") (pintype "passive"))
      (node (ref "C2") (pin "2") (pinfunction "2_2") (pintype "passive"))
      (node (ref "C20") (pin "2") (pinfunction "2_2") (pintype "passive"))
      (node (ref "C21") (pin "+") (pinfunction "+_+") (pintype "passive"))
      (node (ref "C22") (pin "2") (pinfunction "2_2") (pintype "passive"))
      (node (ref "C24") (pin "2") (pinfunction "2_2") (pintype "passive"))
      (node (ref "C25") (pin "2") (pinfunction "2_2") (pintype "passive"))
      (node (ref "C26") (pin "2") (pinfunction "2_2") (pintype "passive"))
      (node (ref "C27") (pin "2") (pinfunction "2_2") (pintype "passive"))
      (node (ref "C28") (pin "1") (pinfunction "1_1") (pintype "passive"))
      (node (ref "C29") (pin "2") (pinfunction "2_2") (pintype "passive"))
      (node (ref "C3") (pin "2") (pinfunction "2_2") (pintype "passive"))
      (node (ref "C30") (pin "2") (pinfunction "2_2") (pintype "passive"))
      (node (ref "C34") (pin "2") (pinfunction "2_2") (pintype "passive"))
      (node (ref "C35") (pin "2") (pinfunction "2_2") (pintype "passive"))
      (node (ref "C36") (pin "1") (pinfunction "1_1") (pintype "passive"))
      (node (ref "C37") (pin "1") (pinfunction "1_1") (pintype "passive"))
      (node (ref "C4") (pin "-") (pinfunction "-_-") (pintype "passive"))
      (node (ref "C41") (pin "1") (pinfunction "1_1") (pintype "passive"))
      (node (ref "C42") (pin "2") (pinfunction "2_2") (pintype "passive"))
      (node (ref "C43") (pin "2") (pinfunction "2_2") (pintype "passive"))
      (node (ref "C45") (pin "1") (pinfunction "1_1") (pintype "passive"))
      (node (ref "C47") (pin "1") (pinfunction "1_1") (pintype "passive"))
      (node (ref "C48") (pin "1") (pinfunction "1_1") (pintype "passive"))
      (node (ref "C5") (pin "-") (pinfunction "-_-") (pintype "passive"))
      (node (ref "C6") (pin "2") (pinfunction "2_2") (pintype "passive"))
      (node (ref "C7") (pin "2") (pinfunction "2_2") (pintype "passive"))
      (node (ref "C8") (pin "2") (pinfunction "2_2") (pintype "passive"))
      (node (ref "D1") (pin "A") (pinfunction "A_A") (pintype "passive"))
      (node (ref "D2") (pin "C") (pinfunction "C_C") (pintype "passive"))
      (node (ref "D3") (pin "1") (pinfunction "A_1") (pintype "passive"))
      (node (ref "IC1") (pin "1") (pinfunction "GND_1") (pintype "power_in"))
      (node (ref "IC10") (pin "8") (pinfunction "GND_8") (pintype "power_in"))
      (node (ref "IC11") (pin "3") (pinfunction "+IN_3") (pintype "input"))
      (node (ref "IC11") (pin "5") (pinfunction "+IN_5") (pintype "input"))
      (node (ref "IC12") (pin "3") (pinfunction "+IN_3") (pintype "input"))
      (node (ref "IC12") (pin "5") (pinfunction "+IN_5") (pintype "input"))
      (node (ref "IC13") (pin "3") (pinfunction "+IN_3") (pintype "input"))
      (node (ref "IC13") (pin "5") (pinfunction "+IN_5") (pintype "input"))
      (node (ref "IC2") (pin "2") (pinfunction "A_2") (pintype "passive"))
      (node (ref "IC3") (pin "6") (pinfunction "GND_6") (pintype "power_in"))
      (node (ref "IC4") (pin "1") (pinfunction "GND_1") (pintype "power_in"))
      (node (ref "IC5") (pin "2") (pinfunction "A_2") (pintype "passive"))
      (node (ref "IC7") (pin "3") (pinfunction "+IN_3") (pintype "input"))
      (node (ref "IC7") (pin "5") (pinfunction "+IN_5") (pintype "input"))
      (node (ref "IC8") (pin "3") (pinfunction "+IN_3") (pintype "input"))
      (node (ref "IC8") (pin "5") (pinfunction "+IN_5") (pintype "input"))
      (node (ref "IC9") (pin "3") (pinfunction "+IN_3") (pintype "input"))
      (node (ref "IC9") (pin "5") (pinfunction "+IN_5") (pintype "input"))
      (node (ref "J1") (pin "GND") (pinfunction "GND_GND") (pintype "passive"))
      (node (ref "J10") (pin "GND") (pinfunction "GND_GND") (pintype "passive"))
      (node (ref "J11") (pin "GND") (pinfunction "GND_GND") (pintype "passive"))
      (node (ref "J12") (pin "GND") (pinfunction "GND_GND") (pintype "passive"))
      (node (ref "J2") (pin "GND") (pinfunction "GND_GND") (pintype "passive"))
      (node (ref "J3") (pin "GND") (pinfunction "GND_GND") (pintype "passive"))
      (node (ref "J4") (pin "GND") (pinfunction "GND_GND") (pintype "passive"))
      (node (ref "J5") (pin "GND") (pinfunction "GND_GND") (pintype "passive"))
      (node (ref "J6") (pin "GND") (pinfunction "GND_GND") (pintype "passive"))
      (node (ref "J7") (pin "GND") (pinfunction "GND_GND") (pintype "passive"))
      (node (ref "J8") (pin "GND") (pinfunction "GND_GND") (pintype "passive"))
      (node (ref "J9") (pin "GND") (pinfunction "GND_GND") (pintype "passive"))
      (node (ref "JP2") (pin "3") (pinfunction "3_3") (pintype "passive"))
      (node (ref "JP2") (pin "4") (pinfunction "4_4") (pintype "passive"))
      (node (ref "JP2") (pin "5") (pinfunction "5_5") (pintype "passive"))
      (node (ref "JP2") (pin "6") (pinfunction "6_6") (pintype "passive"))
      (node (ref "JP2") (pin "7") (pinfunction "7_7") (pintype "passive"))
      (node (ref "JP2") (pin "8") (pinfunction "8_8") (pintype "passive"))
      (node (ref "JP4") (pin "3") (pinfunction "3_3") (pintype "passive"))
      (node (ref "JP4") (pin "5") (pinfunction "5_5") (pintype "passive"))
      (node (ref "JP4") (pin "9") (pinfunction "9_9") (pintype "passive"))
      (node (ref "LED5") (pin "GND") (pinfunction "C_GND") (pintype "bidirectional"))
      (node (ref "LED6") (pin "K") (pinfunction "C_K") (pintype "passive"))
      (node (ref "Q1") (pin "GND") (pinfunction "GND_GND") (pintype "bidirectional"))
      (node (ref "Q2") (pin "E") (pinfunction "E_E") (pintype "passive"))
      (node (ref "R10") (pin "1") (pinfunction "1_1") (pintype "passive"))
      (node (ref "R14") (pin "P$3") (pinfunction "A_P$3") (pintype "passive"))
      (node (ref "R2") (pin "2") (pinfunction "1_2") (pintype "bidirectional"))
      (node (ref "R2") (pin "4") (pinfunction "E_4") (pintype "bidirectional"))
      (node (ref "R24") (pin "1") (pinfunction "1_1") (pintype "passive"))
      (node (ref "R3") (pin "2") (pinfunction "1_2") (pintype "bidirectional"))
      (node (ref "R3") (pin "4") (pinfunction "E_4") (pintype "bidirectional"))
      (node (ref "R4") (pin "2") (pinfunction "1_2") (pintype "bidirectional"))
      (node (ref "R4") (pin "4") (pinfunction "E_4") (pintype "bidirectional"))
      (node (ref "R5") (pin "2") (pinfunction "1_2") (pintype "bidirectional"))
      (node (ref "R5") (pin "4") (pinfunction "E_4") (pintype "bidirectional"))
      (node (ref "R65") (pin "1") (pinfunction "1_1") (pintype "passive"))
      (node (ref "S1") (pin "1") (pinfunction "O_1") (pintype "passive"))
      (node (ref "SW3") (pin "1") (pinfunction "1_1") (pintype "passive"))
      (node (ref "SW3") (pin "2") (pinfunction "2_2") (pintype "passive"))
      (node (ref "SW4") (pin "1") (pinfunction "1_1") (pintype "passive"))
      (node (ref "SW4") (pin "2") (pinfunction "2_2") (pintype "passive"))
      (node (ref "UC1") (pin "20") (pinfunction "PB2/BOOT1_20") (pintype "bidirectional"))
      (node (ref "UC1") (pin "23") (pinfunction "VSS_1_23") (pintype "power_in"))
      (node (ref "UC1") (pin "35") (pinfunction "VSS_2_35") (pintype "power_in"))
      (node (ref "UC1") (pin "47") (pinfunction "VSS_3_47") (pintype "power_in"))
      (node (ref "UC1") (pin "8") (pinfunction "VSS_A_8") (pintype "power_in"))
    )
    (net (code "18") (name "IN_1") (class "Default")
      (node (ref "J2") (pin "TIP") (pinfunction "TIP_TIP") (pintype "passive"))
      (node (ref "R54") (pin "1") (pinfunction "1_1") (pintype "passive"))
    )
    (net (code "19") (name "IN_2") (class "Default")
      (node (ref "J3") (pin "TIP") (pinfunction "TIP_TIP") (pintype "passive"))
      (node (ref "R33") (pin "1") (pinfunction "1_1") (pintype "passive"))
    )
    (net (code "20") (name "IN_3") (class "Default")
      (node (ref "J4") (pin "TIP") (pinfunction "TIP_TIP") (pintype "passive"))
      (node (ref "R36") (pin "1") (pinfunction "1_1") (pintype "passive"))
    )
    (net (code "21") (name "IN_4") (class "Default")
      (node (ref "J5") (pin "TIP") (pinfunction "TIP_TIP") (pintype "passive"))
      (node (ref "R57") (pin "1") (pinfunction "1_1") (pintype "passive"))
    )
    (net (code "22") (name "JTCK") (class "Default")
      (node (ref "JP4") (pin "4") (pinfunction "4_4") (pintype "passive"))
      (node (ref "UC1") (pin "37") (pinfunction "PA14/JTCK/SWCLK_37") (pintype "bidirectional"))
    )
    (net (code "23") (name "JTDI") (class "Default")
      (node (ref "JP4") (pin "8") (pinfunction "8_8") (pintype "passive"))
      (node (ref "UC1") (pin "38") (pinfunction "PA15/JTDI_38") (pintype "bidirectional"))
    )
    (net (code "24") (name "JTDO") (class "Default")
      (node (ref "JP4") (pin "6") (pinfunction "6_6") (pintype "passive"))
      (node (ref "UC1") (pin "39") (pinfunction "PB3/JTDO_39") (pintype "bidirectional"))
    )
    (net (code "25") (name "JTMS") (class "Default")
      (node (ref "JP4") (pin "2") (pinfunction "2_2") (pintype "passive"))
      (node (ref "UC1") (pin "34") (pinfunction "PA13/JTMS/SWDIO_34") (pintype "bidirectional"))
    )
    (net (code "26") (name "LED_B") (class "Default")
      (node (ref "R12") (pin "1") (pinfunction "1_1") (pintype "passive"))
      (node (ref "UC1") (pin "18") (pinfunction "PB0/ADC12_IN8/TIM3_CH3_18") (pintype "bidirectional"))
    )
    (net (code "27") (name "LED_CH1") (class "Default")
      (node (ref "R6") (pin "1") (pinfunction "1_1") (pintype "passive"))
      (node (ref "UC1") (pin "46") (pinfunction "PB9/TIM4_CH4_46") (pintype "input"))
    )
    (net (code "28") (name "LED_CH2") (class "Default")
      (node (ref "R7") (pin "1") (pinfunction "1_1") (pintype "passive"))
      (node (ref "UC1") (pin "45") (pinfunction "PB8/TIM4_CH3_45") (pintype "bidirectional"))
    )
    (net (code "29") (name "LED_CH3") (class "Default")
      (node (ref "R8") (pin "1") (pinfunction "1_1") (pintype "passive"))
      (node (ref "UC1") (pin "43") (pinfunction "PB7/I2C1_SDA/TIM4_CH2_43") (pintype "bidirectional"))
    )
    (net (code "30") (name "LED_CH4") (class "Default")
      (node (ref "R9") (pin "1") (pinfunction "1_1") (pintype "passive"))
      (node (ref "UC1") (pin "42") (pinfunction "PB6/I2C1_SCL/TIM4_CH1_42") (pintype "input"))
    )
    (net (code "31") (name "LED_FRAME") (class "Default")
      (node (ref "R16") (pin "1") (pinfunction "1_1") (pintype "passive"))
      (node (ref "UC1") (pin "41") (pinfunction "PB5/I2C1_SMBA_41") (pintype "input"))
    )
    (net (code "32") (name "LED_G") (class "Default")
      (node (ref "R11") (pin "1") (pinfunction "1_1") (pintype "passive"))
      (node (ref "UC1") (pin "17") (pinfunction "PA7/SPI1_MOSI/ADC12_IN7/TIM3_CH2_17") (pintype "bidirectional"))
    )
    (net (code "33") (name "LED_R") (class "Default")
      (node (ref "R13") (pin "1") (pinfunction "1_1") (pintype "passive"))
      (node (ref "UC1") (pin "19") (pinfunction "PB1/ADC12_IN9/TIM3_CH4_19") (pintype "bidirectional"))
    )
    (net (code "34") (name "MODULATION") (class "Default")
      (node (ref "D3") (pin "3") (pinfunction "AC_3") (pintype "passive"))
      (node (ref "R39") (pin "1") (pinfunction "1_1") (pintype "passive"))
      (node (ref "UC1") (pin "14") (pinfunction "PA4/SPI1_NSS/USART2_CK/ADC12_IN4_14") (pintype "bidirectional"))
    )
    (net (code "35") (name "Net-(C22-Pad1)") (class "Default")
      (node (ref "C22") (pin "1") (pinfunction "1_1") (pintype "passive"))
      (node (ref "R34") (pin "1") (pinfunction "1_1") (pintype "passive"))
    )
    (net (code "36") (name "Net-(C27-Pad1)") (class "Default")
      (node (ref "C27") (pin "1") (pinfunction "1_1") (pintype "passive"))
      (node (ref "R35") (pin "1") (pinfunction "1_1") (pintype "passive"))
    )
    (net (code "37") (name "Net-(C42-Pad1)") (class "Default")
      (node (ref "C42") (pin "1") (pinfunction "1_1") (pintype "passive"))
      (node (ref "R55") (pin "1") (pinfunction "1_1") (pintype "passive"))
    )
    (net (code "38") (name "Net-(C43-Pad1)") (class "Default")
      (node (ref "C43") (pin "1") (pinfunction "1_1") (pintype "passive"))
      (node (ref "R56") (pin "1") (pinfunction "1_1") (pintype "passive"))
    )
    (net (code "39") (name "Net-(IC3-OUTA)") (class "Default")
      (node (ref "IC3") (pin "2") (pinfunction "OUTA_2") (pintype "output"))
      (node (ref "R19") (pin "1") (pinfunction "1_1") (pintype "passive"))
    )
    (net (code "40") (name "Net-(IC3-OUTB)") (class "Default")
      (node (ref "IC3") (pin "3") (pinfunction "OUTB_3") (pintype "output"))
      (node (ref "R20") (pin "1") (pinfunction "1_1") (pintype "passive"))
    )
    (net (code "41") (name "Net-(IC3-OUTC)") (class "Default")
      (node (ref "IC3") (pin "4") (pinfunction "OUTC_4") (pintype "output"))
      (node (ref "R21") (pin "1") (pinfunction "1_1") (pintype "passive"))
    )
    (net (code "42") (name "Net-(IC3-OUTD)") (class "Default")
      (node (ref "IC3") (pin "5") (pinfunction "OUTD_5") (pintype "output"))
      (node (ref "R22") (pin "1") (pinfunction "1_1") (pintype "passive"))
    )
    (net (code "43") (name "Net-(IC5-C)") (class "Default")
      (node (ref "IC5") (pin "1") (pinfunction "C_1") (pintype "passive"))
      (node (ref "IC6") (pin "5") (pinfunction "+IN_5") (pintype "input"))
      (node (ref "R26") (pin "2") (pinfunction "2_2") (pintype "passive"))
      (node (ref "R27") (pin "2") (pinfunction "2_2") (pintype "passive"))
    )
    (net (code "44") (name "Net-(IC6A-+IN)") (class "Default")
      (node (ref "IC6") (pin "3") (pinfunction "+IN_3") (pintype "input"))
      (node (ref "R27") (pin "1") (pinfunction "1_1") (pintype "passive"))
      (node (ref "R65") (pin "2") (pinfunction "2_2") (pintype "passive"))
    )
    (net (code "45") (name "Net-(IC7A--IN)") (class "Default")
      (node (ref "C38") (pin "1") (pinfunction "1_1") (pintype "passive"))
      (node (ref "IC7") (pin "2") (pinfunction "-IN_2") (pintype "input"))
      (node (ref "R43") (pin "1") (pinfunction "1_1") (pintype "passive"))
      (node (ref "R44") (pin "2") (pinfunction "2_2") (pintype "passive"))
      (node (ref "R45") (pin "2") (pinfunction "2_2") (pintype "passive"))
      (node (ref "R46") (pin "2") (pinfunction "2_2") (pintype "passive"))
      (node (ref "R47") (pin "2") (pinfunction "2_2") (pintype "passive"))
    )
    (net (code "46") (name "Net-(IC7A-OUT)") (class "Default")
      (node (ref "C38") (pin "2") (pinfunction "2_2") (pintype "passive"))
      (node (ref "IC7") (pin "1") (pinfunction "OUT_1") (pintype "output"))
      (node (ref "R30") (pin "1") (pinfunction "1_1") (pintype "passive"))
      (node (ref "R43") (pin "2") (pinfunction "2_2") (pintype "passive"))
    )
    (net (code "47") (name "Net-(IC7B--IN)") (class "Default")
      (node (ref "C23") (pin "1") (pinfunction "1_1") (pintype "passive"))
      (node (ref "IC7") (pin "6") (pinfunction "-IN_6") (pintype "input"))
      (node (ref "R29") (pin "1") (pinfunction "1_1") (pintype "passive"))
      (node (ref "R30") (pin "2") (pinfunction "2_2") (pintype "passive"))
    )
    (net (code "48") (name "Net-(IC7B-OUT)") (class "Default")
      (node (ref "C23") (pin "2") (pinfunction "2_2") (pintype "passive"))
      (node (ref "IC7") (pin "7") (pinfunction "OUT_7") (pintype "output"))
      (node (ref "R28") (pin "1") (pinfunction "1_1") (pintype "passive"))
      (node (ref "R29") (pin "2") (pinfunction "2_2") (pintype "passive"))
    )
    (net (code "49") (name "Net-(IC8A--IN)") (class "Default")
      (node (ref "C39") (pin "1") (pinfunction "1_1") (pintype "passive"))
      (node (ref "IC8") (pin "2") (pinfunction "-IN_2") (pintype "input"))
      (node (ref "R49") (pin "1") (pinfunction "1_1") (pintype "passive"))
      (node (ref "R50") (pin "2") (pinfunction "2_2") (pintype "passive"))
    )
    (net (code "50") (name "Net-(IC8A-OUT)") (class "Default")
      (node (ref "C39") (pin "2") (pinfunction "2_2") (pintype "passive"))
      (node (ref "IC8") (pin "1") (pinfunction "OUT_1") (pintype "output"))
      (node (ref "R48") (pin "1") (pinfunction "1_1") (pintype "passive"))
      (node (ref "R49") (pin "2") (pinfunction "2_2") (pintype "passive"))
    )
    (net (code "51") (name "Net-(IC8B-OUT)") (class "Default")
      (node (ref "IC8") (pin "7") (pinfunction "OUT_7") (pintype "output"))
      (node (ref "R31") (pin "2") (pinfunction "2_2") (pintype "passive"))
      (node (ref "R50") (pin "1") (pinfunction "1_1") (pintype "passive"))
    )
    (net (code "52") (name "Net-(IC9A--IN)") (class "Default")
      (node (ref "C40") (pin "1") (pinfunction "1_1") (pintype "passive"))
      (node (ref "IC9") (pin "2") (pinfunction "-IN_2") (pintype "input"))
      (node (ref "R52") (pin "1") (pinfunction "1_1") (pintype "passive"))
      (node (ref "R53") (pin "2") (pinfunction "2_2") (pintype "passive"))
    )
    (net (code "53") (name "Net-(IC9A-OUT)") (class "Default")
      (node (ref "C40") (pin "2") (pinfunction "2_2") (pintype "passive"))
      (node (ref "IC9") (pin "1") (pinfunction "OUT_1") (pintype "output"))
      (node (ref "R51") (pin "1") (pinfunction "1_1") (pintype "passive"))
      (node (ref "R52") (pin "2") (pinfunction "2_2") (pintype "passive"))
    )
    (net (code "54") (name "Net-(IC9B-OUT)") (class "Default")
      (node (ref "IC9") (pin "7") (pinfunction "OUT_7") (pintype "output"))
      (node (ref "R32") (pin "2") (pinfunction "2_2") (pintype "passive"))
      (node (ref "R53") (pin "1") (pinfunction "1_1") (pintype "passive"))
    )
    (net (code "55") (name "Net-(IC10A-IN)") (class "Default")
      (node (ref "IC10") (pin "2") (pinfunction "IN_2") (pintype "input"))
      (node (ref "R54") (pin "2") (pinfunction "2_2") (pintype "passive"))
      (node (ref "R55") (pin "2") (pinfunction "2_2") (pintype "passive"))
    )
    (net (code "56") (name "Net-(IC10A-OUT)") (class "Default")
      (node (ref "IC10") (pin "4") (pinfunction "OUT_4") (pintype "output"))
      (node (ref "IC8") (pin "6") (pinfunction "-IN_6") (pintype "input"))
      (node (ref "R31") (pin "1") (pinfunction "1_1") (pintype "passive"))
    )
    (net (code "57") (name "Net-(IC10B-IN)") (class "Default")
      (node (ref "IC10") (pin "7") (pinfunction "IN_7") (pintype "input"))
      (node (ref "R56") (pin "2") (pinfunction "2_2") (pintype "passive"))
      (node (ref "R57") (pin "2") (pinfunction "2_2") (pintype "passive"))
    )
    (net (code "58") (name "Net-(IC10B-OUT)") (class "Default")
      (node (ref "IC10") (pin "5") (pinfunction "OUT_5") (pintype "output"))
      (node (ref "IC12") (pin "6") (pinfunction "-IN_6") (pintype "input"))
      (node (ref "R38") (pin "1") (pinfunction "1_1") (pintype "passive"))
    )
    (net (code "59") (name "Net-(IC10C-IN)") (class "Default")
      (node (ref "IC10") (pin "10") (pinfunction "IN_10") (pintype "input"))
      (node (ref "R35") (pin "2") (pinfunction "2_2") (pintype "passive"))
      (node (ref "R36") (pin "2") (pinfunction "2_2") (pintype "passive"))
    )
    (net (code "60") (name "Net-(IC10C-OUT)") (class "Default")
      (node (ref "IC10") (pin "12") (pinfunction "OUT_12") (pintype "output"))
      (node (ref "IC11") (pin "6") (pinfunction "-IN_6") (pintype "input"))
      (node (ref "R37") (pin "1") (pinfunction "1_1") (pintype "passive"))
    )
    (net (code "61") (name "Net-(IC10D-IN)") (class "Default")
      (node (ref "IC10") (pin "15") (pinfunction "IN_15") (pintype "input"))
      (node (ref "R33") (pin "2") (pinfunction "2_2") (pintype "passive"))
      (node (ref "R34") (pin "2") (pinfunction "2_2") (pintype "passive"))
    )
    (net (code "62") (name "Net-(IC10D-OUT)") (class "Default")
      (node (ref "IC10") (pin "13") (pinfunction "OUT_13") (pintype "output"))
      (node (ref "IC9") (pin "6") (pinfunction "-IN_6") (pintype "input"))
      (node (ref "R32") (pin "1") (pinfunction "1_1") (pintype "passive"))
    )
    (net (code "63") (name "Net-(IC11A--IN)") (class "Default")
      (node (ref "C44") (pin "1") (pinfunction "1_1") (pintype "passive"))
      (node (ref "IC11") (pin "2") (pinfunction "-IN_2") (pintype "input"))
      (node (ref "R59") (pin "1") (pinfunction "1_1") (pintype "passive"))
      (node (ref "R60") (pin "2") (pinfunction "2_2") (pintype "passive"))
    )
    (net (code "64") (name "Net-(IC11A-OUT)") (class "Default")
      (node (ref "C44") (pin "2") (pinfunction "2_2") (pintype "passive"))
      (node (ref "IC11") (pin "1") (pinfunction "OUT_1") (pintype "output"))
      (node (ref "R58") (pin "1") (pinfunction "1_1") (pintype "passive"))
      (node (ref "R59") (pin "2") (pinfunction "2_2") (pintype "passive"))
    )
    (net (code "65") (name "Net-(IC11B-OUT)") (class "Default")
      (node (ref "IC11") (pin "7") (pinfunction "OUT_7") (pintype "output"))
      (node (ref "R37") (pin "2") (pinfunction "2_2") (pintype "passive"))
      (node (ref "R60") (pin "1") (pinfunction "1_1") (pintype "passive"))
    )
    (net (code "66") (name "Net-(IC12A--IN)") (class "Default")
      (node (ref "C46") (pin "1") (pinfunction "1_1") (pintype "passive"))
      (node (ref "IC12") (pin "2") (pinfunction "-IN_2") (pintype "input"))
      (node (ref "R62") (pin "1") (pinfunction "1_1") (pintype "passive"))
      (node (ref "R63") (pin "2") (pinfunction "2_2") (pintype "passive"))
    )
    (net (code "67") (name "Net-(IC12A-OUT)") (class "Default")
      (node (ref "C46") (pin "2") (pinfunction "2_2") (pintype "passive"))
      (node (ref "IC12") (pin "1") (pinfunction "OUT_1") (pintype "output"))
      (node (ref "R61") (pin "1") (pinfunction "1_1") (pintype "passive"))
      (node (ref "R62") (pin "2") (pinfunction "2_2") (pintype "passive"))
    )
    (net (code "68") (name "Net-(IC12B-OUT)") (class "Default")
      (node (ref "IC12") (pin "7") (pinfunction "OUT_7") (pintype "output"))
      (node (ref "R38") (pin "2") (pinfunction "2_2") (pintype "passive"))
      (node (ref "R63") (pin "1") (pinfunction "1_1") (pintype "passive"))
    )
    (net (code "69") (name "Net-(IC13A--IN)") (class "Default")
      (node (ref "IC13") (pin "2") (pinfunction "-IN_2") (pintype "input"))
      (node (ref "R15") (pin "P$3") (pinfunction "3_P$3") (pintype "passive"))
      (node (ref "R64") (pin "2") (pinfunction "2_2") (pintype "passive"))
    )
    (net (code "70") (name "Net-(IC13A-OUT)") (class "Default")
      (node (ref "IC13") (pin "1") (pinfunction "OUT_1") (pintype "output"))
      (node (ref "R41") (pin "2") (pinfunction "2_2") (pintype "passive"))
      (node (ref "R64") (pin "1") (pinfunction "1_1") (pintype "passive"))
    )
    (net (code "71") (name "Net-(IC13B--IN)") (class "Default")
      (node (ref "C31") (pin "1") (pinfunction "1_1") (pintype "passive"))
      (node (ref "IC13") (pin "6") (pinfunction "-IN_6") (pintype "input"))
      (node (ref "R15") (pin "P$1") (pinfunction "1_P$1") (pintype "passive"))
      (node (ref "R40") (pin "2") (pinfunction "2_2") (pintype "passive"))
      (node (ref "R41") (pin "1") (pinfunction "1_1") (pintype "passive"))
      (node (ref "R42") (pin "1") (pinfunction "1_1") (pintype "passive"))
    )
    (net (code "72") (name "Net-(IC13B-OUT)") (class "Default")
      (node (ref "C31") (pin "2") (pinfunction "2_2") (pintype "passive"))
      (node (ref "IC13") (pin "7") (pinfunction "OUT_7") (pintype "output"))
      (node (ref "R39") (pin "2") (pinfunction "2_2") (pintype "passive"))
      (node (ref "R40") (pin "1") (pinfunction "1_1") (pintype "passive"))
    )
    (net (code "73") (name "Net-(J6-PadTIP)") (class "Default")
      (node (ref "J6") (pin "TIP") (pinfunction "TIP_TIP") (pintype "passive"))
      (node (ref "R18") (pin "1") (pinfunction "1_1") (pintype "passive"))
    )
    (net (code "74") (name "Net-(J7-PadTIP)") (class "Default")
      (node (ref "J7") (pin "TIP") (pinfunction "TIP_TIP") (pintype "passive"))
      (node (ref "R28") (pin "2") (pinfunction "2_2") (pintype "passive"))
    )
    (net (code "75") (name "Net-(J8-PadTIP)") (class "Default")
      (node (ref "J8") (pin "TIP") (pinfunction "TIP_TIP") (pintype "passive"))
      (node (ref "R48") (pin "2") (pinfunction "2_2") (pintype "passive"))
    )
    (net (code "76") (name "Net-(J9-PadTIP)") (class "Default")
      (node (ref "J9") (pin "TIP") (pinfunction "TIP_TIP") (pintype "passive"))
      (node (ref "R51") (pin "2") (pinfunction "2_2") (pintype "passive"))
    )
    (net (code "77") (name "Net-(J10-PadTIP)") (class "Default")
      (node (ref "J10") (pin "TIP") (pinfunction "TIP_TIP") (pintype "passive"))
      (node (ref "R58") (pin "2") (pinfunction "2_2") (pintype "passive"))
    )
    (net (code "78") (name "Net-(J11-PadTIP)") (class "Default")
      (node (ref "J11") (pin "TIP") (pinfunction "TIP_TIP") (pintype "passive"))
      (node (ref "R61") (pin "2") (pinfunction "2_2") (pintype "passive"))
    )
    (net (code "79") (name "Net-(J12-PadTIP)") (class "Default")
      (node (ref "J12") (pin "TIP") (pinfunction "TIP_TIP") (pintype "passive"))
      (node (ref "Q2") (pin "C") (pinfunction "C_C") (pintype "passive"))
      (node (ref "R24") (pin "2") (pinfunction "2_2") (pintype "passive"))
      (node (ref "R25") (pin "1") (pinfunction "1_1") (pintype "passive"))
    )
    (net (code "80") (name "Net-(JP2-Pad1)") (class "Default")
      (node (ref "JP2") (pin "1") (pinfunction "1_1") (pintype "passive"))
      (node (ref "JP2") (pin "2") (pinfunction "2_2") (pintype "passive"))
      (node (ref "P1") (pin "2") (pinfunction "2_2") (pintype "bidirectional"))
    )
    (net (code "81") (name "Net-(JP2-Pad10)") (class "Default")
      (node (ref "JP2") (pin "10") (pinfunction "10_10") (pintype "passive"))
      (node (ref "JP2") (pin "9") (pinfunction "9_9") (pintype "passive"))
      (node (ref "P2") (pin "2") (pinfunction "2_2") (pintype "bidirectional"))
    )
    (net (code "82") (name "Net-(LED5-PadBLU)") (class "Default")
      (node (ref "LED5") (pin "BLU") (pinfunction "BLU_BLU") (pintype "bidirectional"))
      (node (ref "R12") (pin "2") (pinfunction "2_2") (pintype "passive"))
    )
    (net (code "83") (name "Net-(LED5-PadGRN)") (class "Default")
      (node (ref "LED5") (pin "GRN") (pinfunction "GRN_GRN") (pintype "bidirectional"))
      (node (ref "R11") (pin "2") (pinfunction "2_2") (pintype "passive"))
    )
    (net (code "84") (name "Net-(LED5-PadRED)") (class "Default")
      (node (ref "LED5") (pin "RED") (pinfunction "RED_RED") (pintype "bidirectional"))
      (node (ref "R13") (pin "2") (pinfunction "2_2") (pintype "passive"))
    )
    (net (code "85") (name "Net-(LED6-PadA)") (class "Default")
      (node (ref "LED6") (pin "A") (pinfunction "A_A") (pintype "passive"))
      (node (ref "R16") (pin "2") (pinfunction "2_2") (pintype "passive"))
    )
    (net (code "86") (name "Net-(Q2-PadB)") (class "Default")
      (node (ref "Q2") (pin "B") (pinfunction "B_B") (pintype "passive"))
      (node (ref "R23") (pin "2") (pinfunction "2_2") (pintype "passive"))
    )
    (net (code "87") (name "Net-(R2-B)") (class "Default")
      (node (ref "R2") (pin "5") (pinfunction "B_5") (pintype "bidirectional"))
      (node (ref "R6") (pin "2") (pinfunction "2_2") (pintype "passive"))
    )
    (net (code "88") (name "Net-(R3-B)") (class "Default")
      (node (ref "R3") (pin "5") (pinfunction "B_5") (pintype "bidirectional"))
      (node (ref "R7") (pin "2") (pinfunction "2_2") (pintype "passive"))
    )
    (net (code "89") (name "Net-(R4-B)") (class "Default")
      (node (ref "R4") (pin "5") (pinfunction "B_5") (pintype "bidirectional"))
      (node (ref "R8") (pin "2") (pinfunction "2_2") (pintype "passive"))
    )
    (net (code "90") (name "Net-(R5-B)") (class "Default")
      (node (ref "R5") (pin "5") (pinfunction "B_5") (pintype "bidirectional"))
      (node (ref "R9") (pin "2") (pinfunction "2_2") (pintype "passive"))
    )
    (net (code "91") (name "Net-(R15-2)") (class "Default")
      (node (ref "R15") (pin "P$2") (pinfunction "2_P$2") (pintype "passive"))
      (node (ref "R18") (pin "2") (pinfunction "2_2") (pintype "passive"))
    )
    (net (code "92") (name "Net-(S1-P)") (class "Default")
      (node (ref "J1") (pin "NORM") (pinfunction "NORM_NORM") (pintype "passive"))
      (node (ref "S1") (pin "2") (pinfunction "P_2") (pintype "passive"))
    )
    (net (code "93") (name "Net-(S1-S)") (class "Default")
      (node (ref "JP1") (pin "2") (pinfunction "2_2") (pintype "passive"))
      (node (ref "S1") (pin "3") (pinfunction "S_3") (pintype "passive"))
    )
    (net (code "94") (name "Net-(UC1-PD0-OSC_IN)") (class "Default")
      (node (ref "Q1") (pin "X1") (pinfunction "X1_X1") (pintype "bidirectional"))
      (node (ref "UC1") (pin "5") (pinfunction "PD0-OSC_IN_5") (pintype "input"))
    )
    (net (code "95") (name "Net-(UC1-PD1-OSC_OUT)") (class "Default")
      (node (ref "Q1") (pin "X2") (pinfunction "X2_X2") (pintype "bidirectional"))
      (node (ref "UC1") (pin "6") (pinfunction "PD1-OSC_OUT_6") (pintype "input"))
    )
    (net (code "96") (name "PAN") (class "Default")
      (node (ref "J1") (pin "TIP") (pinfunction "TIP_TIP") (pintype "passive"))
      (node (ref "J2") (pin "NORM") (pinfunction "NORM_NORM") (pintype "passive"))
      (node (ref "J3") (pin "NORM") (pinfunction "NORM_NORM") (pintype "passive"))
      (node (ref "J4") (pin "NORM") (pinfunction "NORM_NORM") (pintype "passive"))
      (node (ref "J5") (pin "NORM") (pinfunction "NORM_NORM") (pintype "passive"))
    )
    (net (code "97") (name "POT_CH1") (class "Default")
      (node (ref "R2") (pin "1") (pinfunction "2_1") (pintype "bidirectional"))
      (node (ref "UC1") (pin "10") (pinfunction "PA0_WKUP/USART2_CTS/ADC12_IN0/TIM2_CH1_ETR_10") (pintype "bidirectional"))
    )
    (net (code "98") (name "POT_CH2") (class "Default")
      (node (ref "R3") (pin "1") (pinfunction "2_1") (pintype "bidirectional"))
      (node (ref "UC1") (pin "11") (pinfunction "PA1/USART2_RTS/ADC12_IN1/TIM2_CH2_11") (pintype "bidirectional"))
    )
    (net (code "99") (name "POT_CH3") (class "Default")
      (node (ref "R4") (pin "1") (pinfunction "2_1") (pintype "bidirectional"))
      (node (ref "UC1") (pin "12") (pinfunction "PA2/USART2_TX/ADC12_IN2/TIM2_CH3_12") (pintype "bidirectional"))
    )
    (net (code "100") (name "POT_CH4") (class "Default")
      (node (ref "R5") (pin "1") (pinfunction "2_1") (pintype "bidirectional"))
      (node (ref "UC1") (pin "13") (pinfunction "PA3/USART2_RX/ADC12_IN3/TIM2_CH4_13") (pintype "bidirectional"))
    )
    (net (code "101") (name "POT_FRAME") (class "Default")
      (node (ref "R14") (pin "P$2") (pinfunction "S_P$2") (pintype "passive"))
      (node (ref "UC1") (pin "15") (pinfunction "PA5/SPI1_SCK/ADC12_IN5_15") (pintype "bidirectional"))
    )
    (net (code "102") (name "RESET") (class "Default")
      (node (ref "JP4") (pin "10") (pinfunction "10_10") (pintype "passive"))
      (node (ref "R1") (pin "1") (pinfunction "1_1") (pintype "passive"))
      (node (ref "UC1") (pin "7") (pinfunction "NRST_7") (pintype "input"))
    )
    (net (code "103") (name "RX") (class "Default")
      (node (ref "UC1") (pin "31") (pinfunction "PA10/USART1_RX/TIM1_CH3_31") (pintype "bidirectional"))
    )
    (net (code "104") (name "TX") (class "Default")
      (node (ref "UC1") (pin "30") (pinfunction "PA9/USART1_TX/TIM1_CH2_30") (pintype "input"))
    )
    (net (code "105") (name "VCA_1") (class "Default")
      (node (ref "J8") (pin "NORM") (pinfunction "NORM_NORM") (pintype "passive"))
      (node (ref "R44") (pin "1") (pinfunction "1_1") (pintype "passive"))
    )
    (net (code "106") (name "VCA_2") (class "Default")
      (node (ref "J9") (pin "NORM") (pinfunction "NORM_NORM") (pintype "passive"))
      (node (ref "R47") (pin "1") (pinfunction "1_1") (pintype "passive"))
    )
    (net (code "107") (name "VCA_3") (class "Default")
      (node (ref "J10") (pin "NORM") (pinfunction "NORM_NORM") (pintype "passive"))
      (node (ref "R46") (pin "1") (pinfunction "1_1") (pintype "passive"))
    )
    (net (code "108") (name "VCA_4") (class "Default")
      (node (ref "J11") (pin "NORM") (pinfunction "NORM_NORM") (pintype "passive"))
      (node (ref "R45") (pin "1") (pinfunction "1_1") (pintype "passive"))
    )
    (net (code "109") (name "VCC") (class "Default")
      (node (ref "C11") (pin "+") (pinfunction "+_+") (pintype "passive"))
      (node (ref "C24") (pin "1") (pinfunction "1_1") (pintype "passive"))
      (node (ref "C25") (pin "1") (pinfunction "1_1") (pintype "passive"))
      (node (ref "C26") (pin "1") (pinfunction "1_1") (pintype "passive"))
      (node (ref "C29") (pin "1") (pinfunction "1_1") (pintype "passive"))
      (node (ref "C30") (pin "1") (pinfunction "1_1") (pintype "passive"))
      (node (ref "C34") (pin "1") (pinfunction "1_1") (pintype "passive"))
      (node (ref "C35") (pin "1") (pinfunction "1_1") (pintype "passive"))
      (node (ref "C4") (pin "+") (pinfunction "+_+") (pintype "passive"))
      (node (ref "D1") (pin "C") (pinfunction "C_C") (pintype "passive"))
      (node (ref "IC1") (pin "3") (pinfunction "VIN_3") (pintype "input"))
      (node (ref "IC10") (pin "16") (pinfunction "V+_16") (pintype "power_in"))
      (node (ref "IC11") (pin "8") (pinfunction "V+_8") (pintype "power_in"))
      (node (ref "IC12") (pin "8") (pinfunction "V+_8") (pintype "power_in"))
      (node (ref "IC13") (pin "8") (pinfunction "V+_8") (pintype "power_in"))
      (node (ref "IC4") (pin "3") (pinfunction "VIN_3") (pintype "input"))
      (node (ref "IC6") (pin "8") (pinfunction "V+_8") (pintype "power_in"))
      (node (ref "IC7") (pin "8") (pinfunction "V+_8") (pintype "power_in"))
      (node (ref "IC8") (pin "8") (pinfunction "V+_8") (pintype "power_in"))
      (node (ref "IC9") (pin "8") (pinfunction "V+_8") (pintype "power_in"))
      (node (ref "P1") (pin "1") (pinfunction "1_1") (pintype "bidirectional"))
      (node (ref "R25") (pin "2") (pinfunction "2_2") (pintype "passive"))
      (node (ref "R26") (pin "1") (pinfunction "1_1") (pintype "passive"))
    )
    (net (code "110") (name "VEE") (class "Default")
      (node (ref "C21") (pin "-") (pinfunction "-_-") (pintype "passive"))
      (node (ref "C28") (pin "2") (pinfunction "2_2") (pintype "passive"))
      (node (ref "C36") (pin "2") (pinfunction "2_2") (pintype "passive"))
      (node (ref "C37") (pin "2") (pinfunction "2_2") (pintype "passive"))
      (node (ref "C41") (pin "2") (pinfunction "2_2") (pintype "passive"))
      (node (ref "C45") (pin "2") (pinfunction "2_2") (pintype "passive"))
      (node (ref "C47") (pin "2") (pinfunction "2_2") (pintype "passive"))
      (node (ref "C48") (pin "2") (pinfunction "2_2") (pintype "passive"))
      (node (ref "D2") (pin "A") (pinfunction "A_A") (pintype "passive"))
      (node (ref "IC10") (pin "9") (pinfunction "V-_9") (pintype "power_in"))
      (node (ref "IC11") (pin "4") (pinfunction "V-_4") (pintype "power_in"))
      (node (ref "IC12") (pin "4") (pinfunction "V-_4") (pintype "power_in"))
      (node (ref "IC13") (pin "4") (pinfunction "V-_4") (pintype "power_in"))
      (node (ref "IC6") (pin "4") (pinfunction "V-_4") (pintype "power_in"))
      (node (ref "IC7") (pin "4") (pinfunction "V-_4") (pintype "power_in"))
      (node (ref "IC8") (pin "4") (pinfunction "V-_4") (pintype "power_in"))
      (node (ref "IC9") (pin "4") (pinfunction "V-_4") (pintype "power_in"))
      (node (ref "P2") (pin "1") (pinfunction "1_1") (pintype "bidirectional"))
      (node (ref "R42") (pin "2") (pinfunction "2_2") (pintype "passive"))
    )
    (net (code "111") (name "unconnected-(IC10E-MODE-Pad1)") (class "Default")
      (node (ref "IC10") (pin "1") (pinfunction "MODE_1") (pintype "input"))
    )
    (net (code "112") (name "unconnected-(J6-PadNORM)") (class "Default")
      (node (ref "J6") (pin "NORM") (pinfunction "NORM_NORM") (pintype "passive"))
    )
    (net (code "113") (name "unconnected-(J7-PadNORM)") (class "Default")
      (node (ref "J7") (pin "NORM") (pinfunction "NORM_NORM") (pintype "passive"))
    )
    (net (code "114") (name "unconnected-(J12-PadNORM)") (class "Default")
      (node (ref "J12") (pin "NORM") (pinfunction "NORM_NORM") (pintype "passive"))
    )
    (net (code "115") (name "unconnected-(JP4-Pad7)") (class "Default")
      (node (ref "JP4") (pin "7") (pinfunction "7_7") (pintype "passive"))
    )
    (net (code "116") (name "unconnected-(R2-L-Pad3)") (class "Default")
      (node (ref "R2") (pin "3") (pinfunction "L_3") (pintype "bidirectional"))
    )
    (net (code "117") (name "unconnected-(R3-L-Pad3)") (class "Default")
      (node (ref "R3") (pin "3") (pinfunction "L_3") (pintype "bidirectional"))
    )
    (net (code "118") (name "unconnected-(R4-L-Pad3)") (class "Default")
      (node (ref "R4") (pin "3") (pinfunction "L_3") (pintype "bidirectional"))
    )
    (net (code "119") (name "unconnected-(R5-L-Pad3)") (class "Default")
      (node (ref "R5") (pin "3") (pinfunction "L_3") (pintype "bidirectional"))
    )
    (net (code "120") (name "unconnected-(UC1-PA8{slash}USART1_CK{slash}TIM1_CH1{slash}MCO-Pad29)") (class "Default")
      (node (ref "UC1") (pin "29") (pinfunction "PA8/USART1_CK/TIM1_CH1/MCO_29") (pintype "bidirectional"))
    )
    (net (code "121") (name "unconnected-(UC1-PA11{slash}USART1_CTS{slash}CAN_RX{slash}TIM1_CH4{slash}USBDM-Pad32)") (class "Default")
      (node (ref "UC1") (pin "32") (pinfunction "PA11/USART1_CTS/CAN_RX/TIM1_CH4/USBDM_32") (pintype "bidirectional"))
    )
    (net (code "122") (name "unconnected-(UC1-PA12{slash}USART1_RTS{slash}CAN_TX{slash}TIM1_ETR{slash}USBDP-Pad33)") (class "Default")
      (node (ref "UC1") (pin "33") (pinfunction "PA12/USART1_RTS/CAN_TX/TIM1_ETR/USBDP_33") (pintype "bidirectional"))
    )
    (net (code "123") (name "unconnected-(UC1-PB4{slash}NJTRST-Pad40)") (class "Default")
      (node (ref "UC1") (pin "40") (pinfunction "PB4/NJTRST_40") (pintype "bidirectional"))
    )
    (net (code "124") (name "unconnected-(UC1-PB14{slash}SPI2_MISO{slash}USART3_RTS{slash}TIM1_CH2N-Pad27)") (class "Default")
      (node (ref "UC1") (pin "27") (pinfunction "PB14/SPI2_MISO/USART3_RTS/TIM1_CH2N_27") (pintype "input"))
    )
    (net (code "125") (name "unconnected-(UC1-PC13-TAMPER-RTC-Pad2)") (class "Default")
      (node (ref "UC1") (pin "2") (pinfunction "PC13-TAMPER-RTC_2") (pintype "input"))
    )
    (net (code "126") (name "unconnected-(UC1-PC14-OSC32_IN-Pad3)") (class "Default")
      (node (ref "UC1") (pin "3") (pinfunction "PC14-OSC32_IN_3") (pintype "input"))
    )
    (net (code "127") (name "unconnected-(UC1-PC15-OSC32_OUT-Pad4)") (class "Default")
      (node (ref "UC1") (pin "4") (pinfunction "PC15-OSC32_OUT_4") (pintype "input"))
    )
  )
)
